# Controller_Board.net
KiCad netlist of a schematic drawn in EAGLE
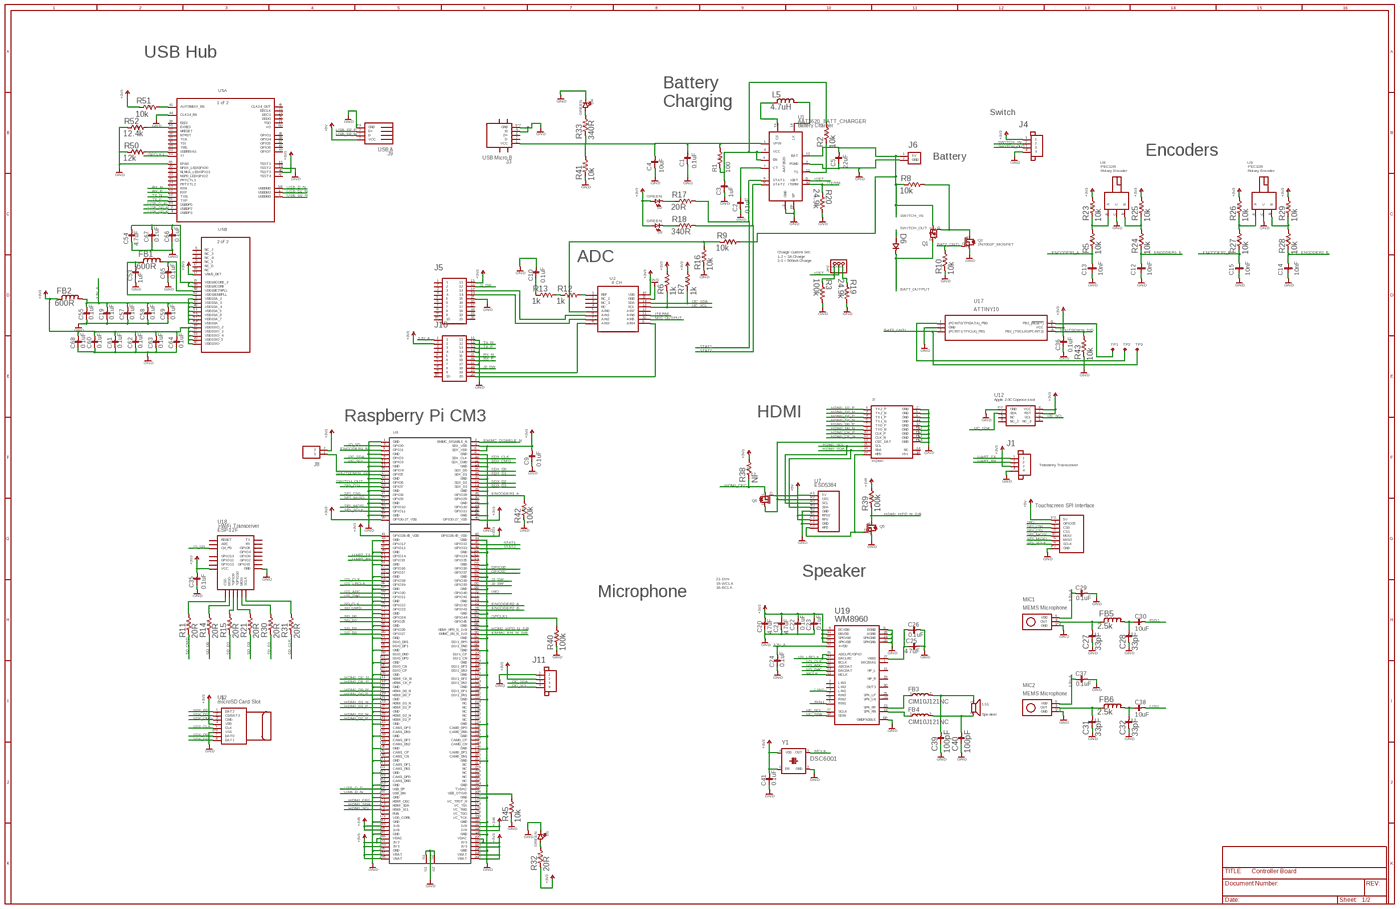
[diagram p0: schematic, sheet 1, overview]
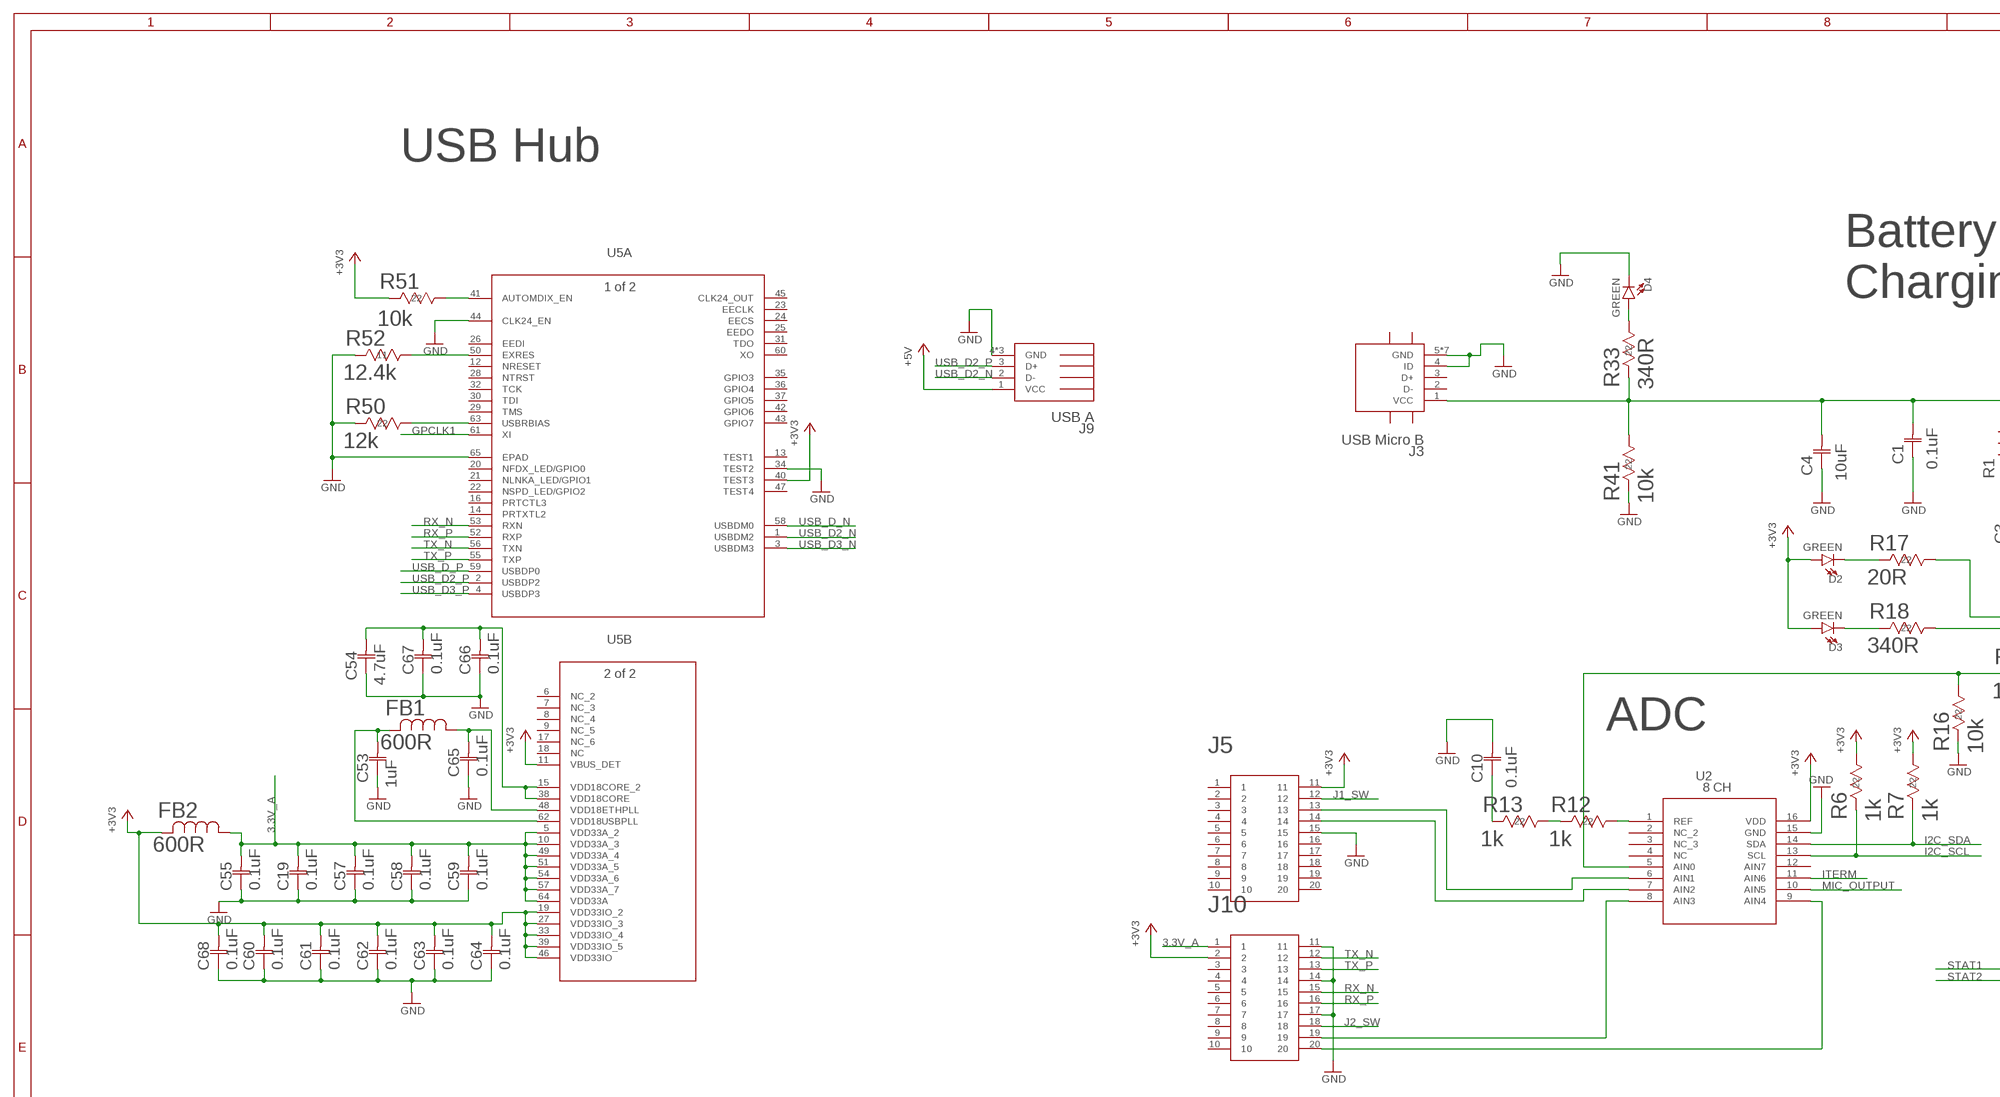
[diagram p1: schematic, sheet 1, part 1 of 4]
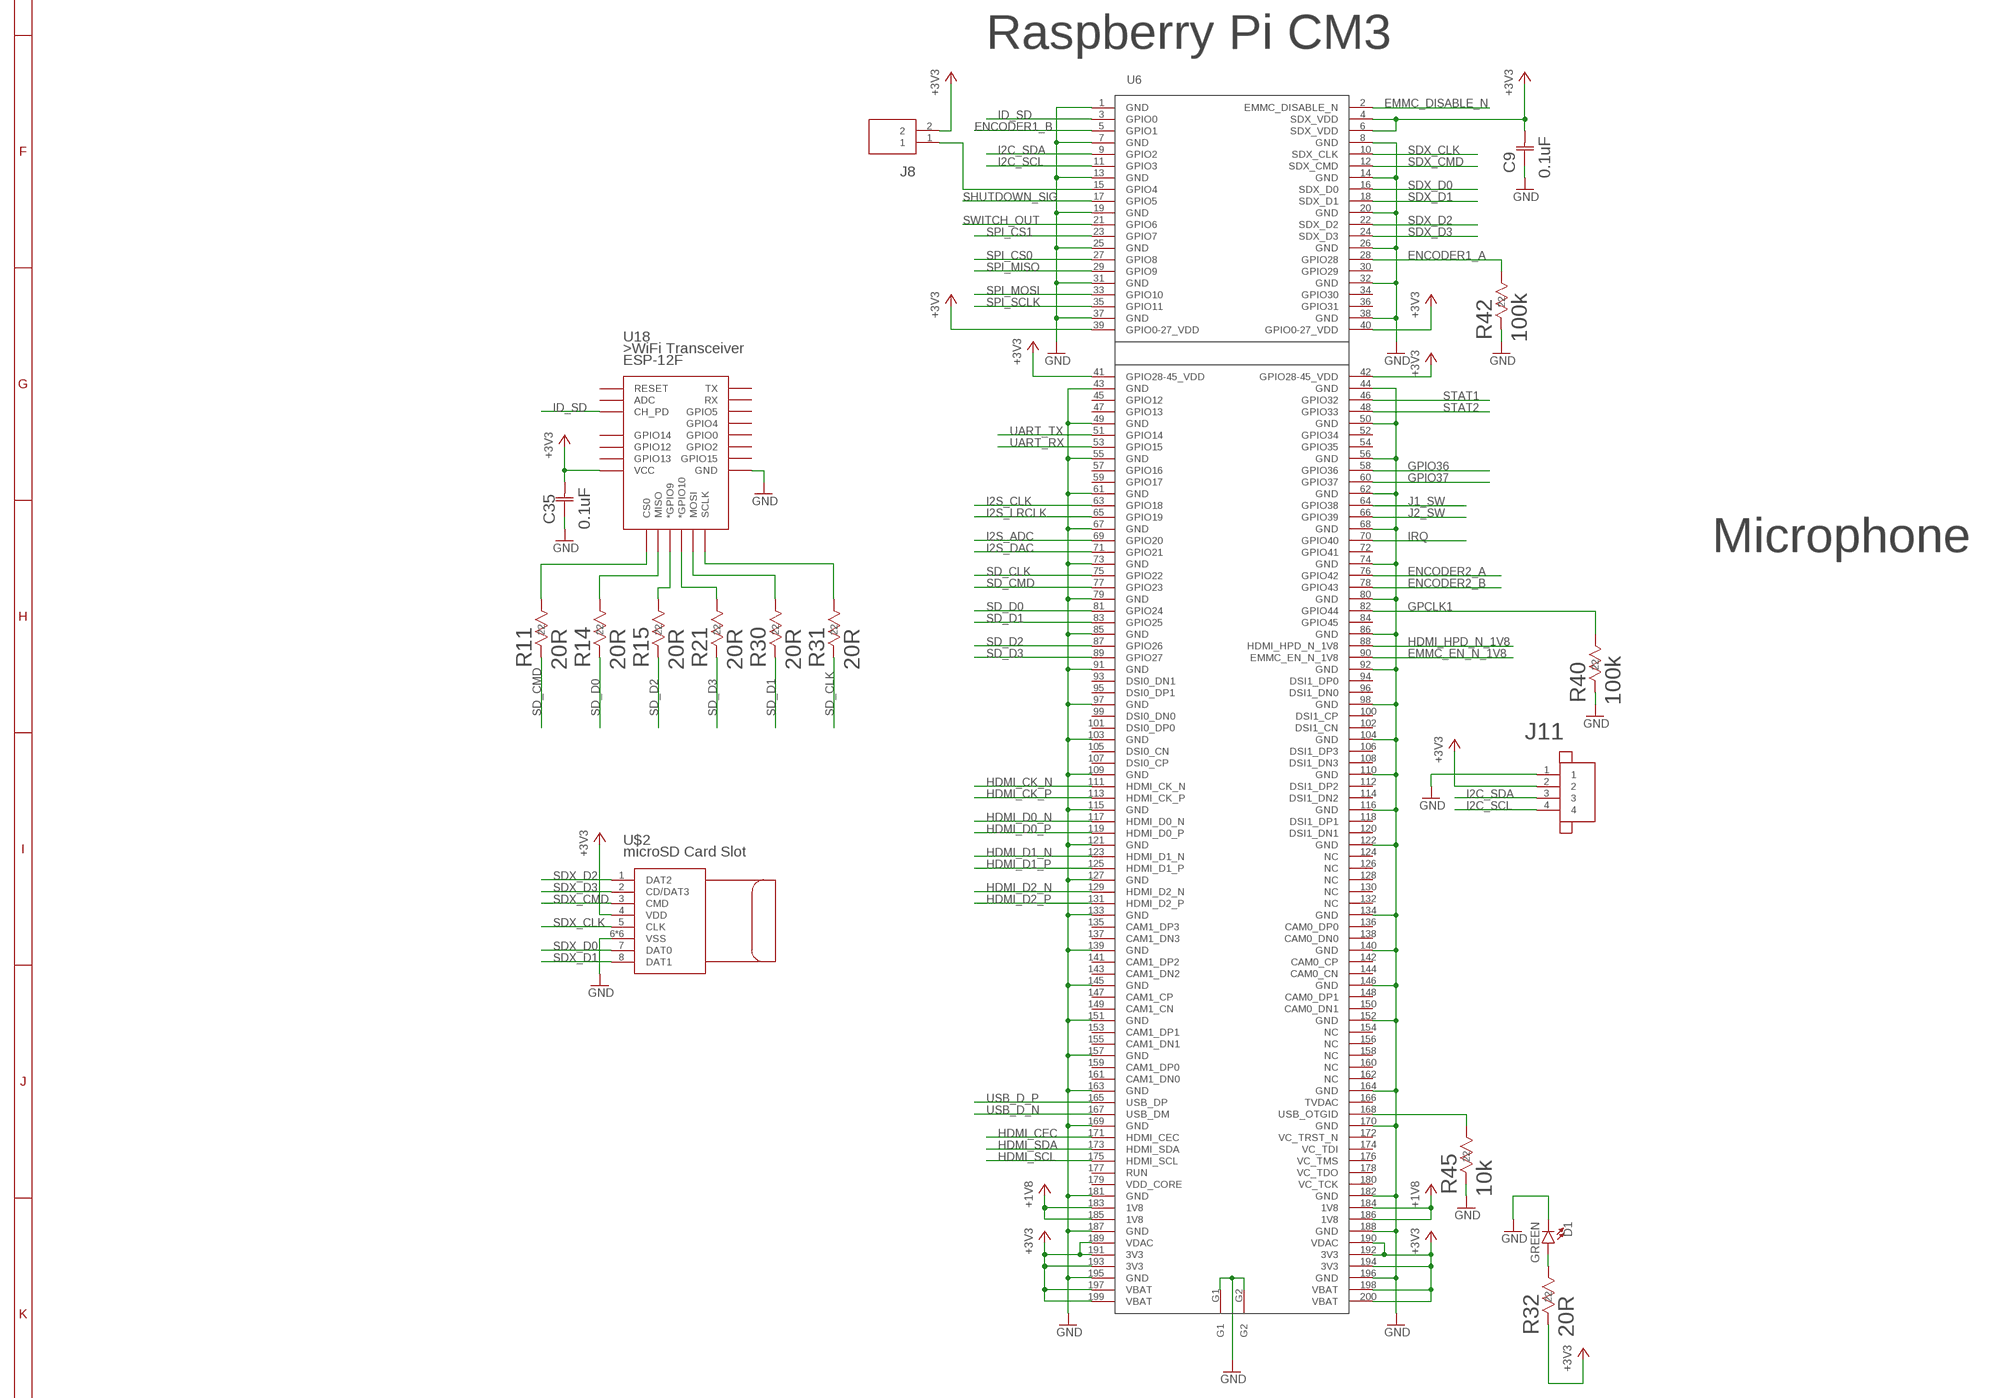
[diagram p2: schematic, sheet 1, part 2 of 4]
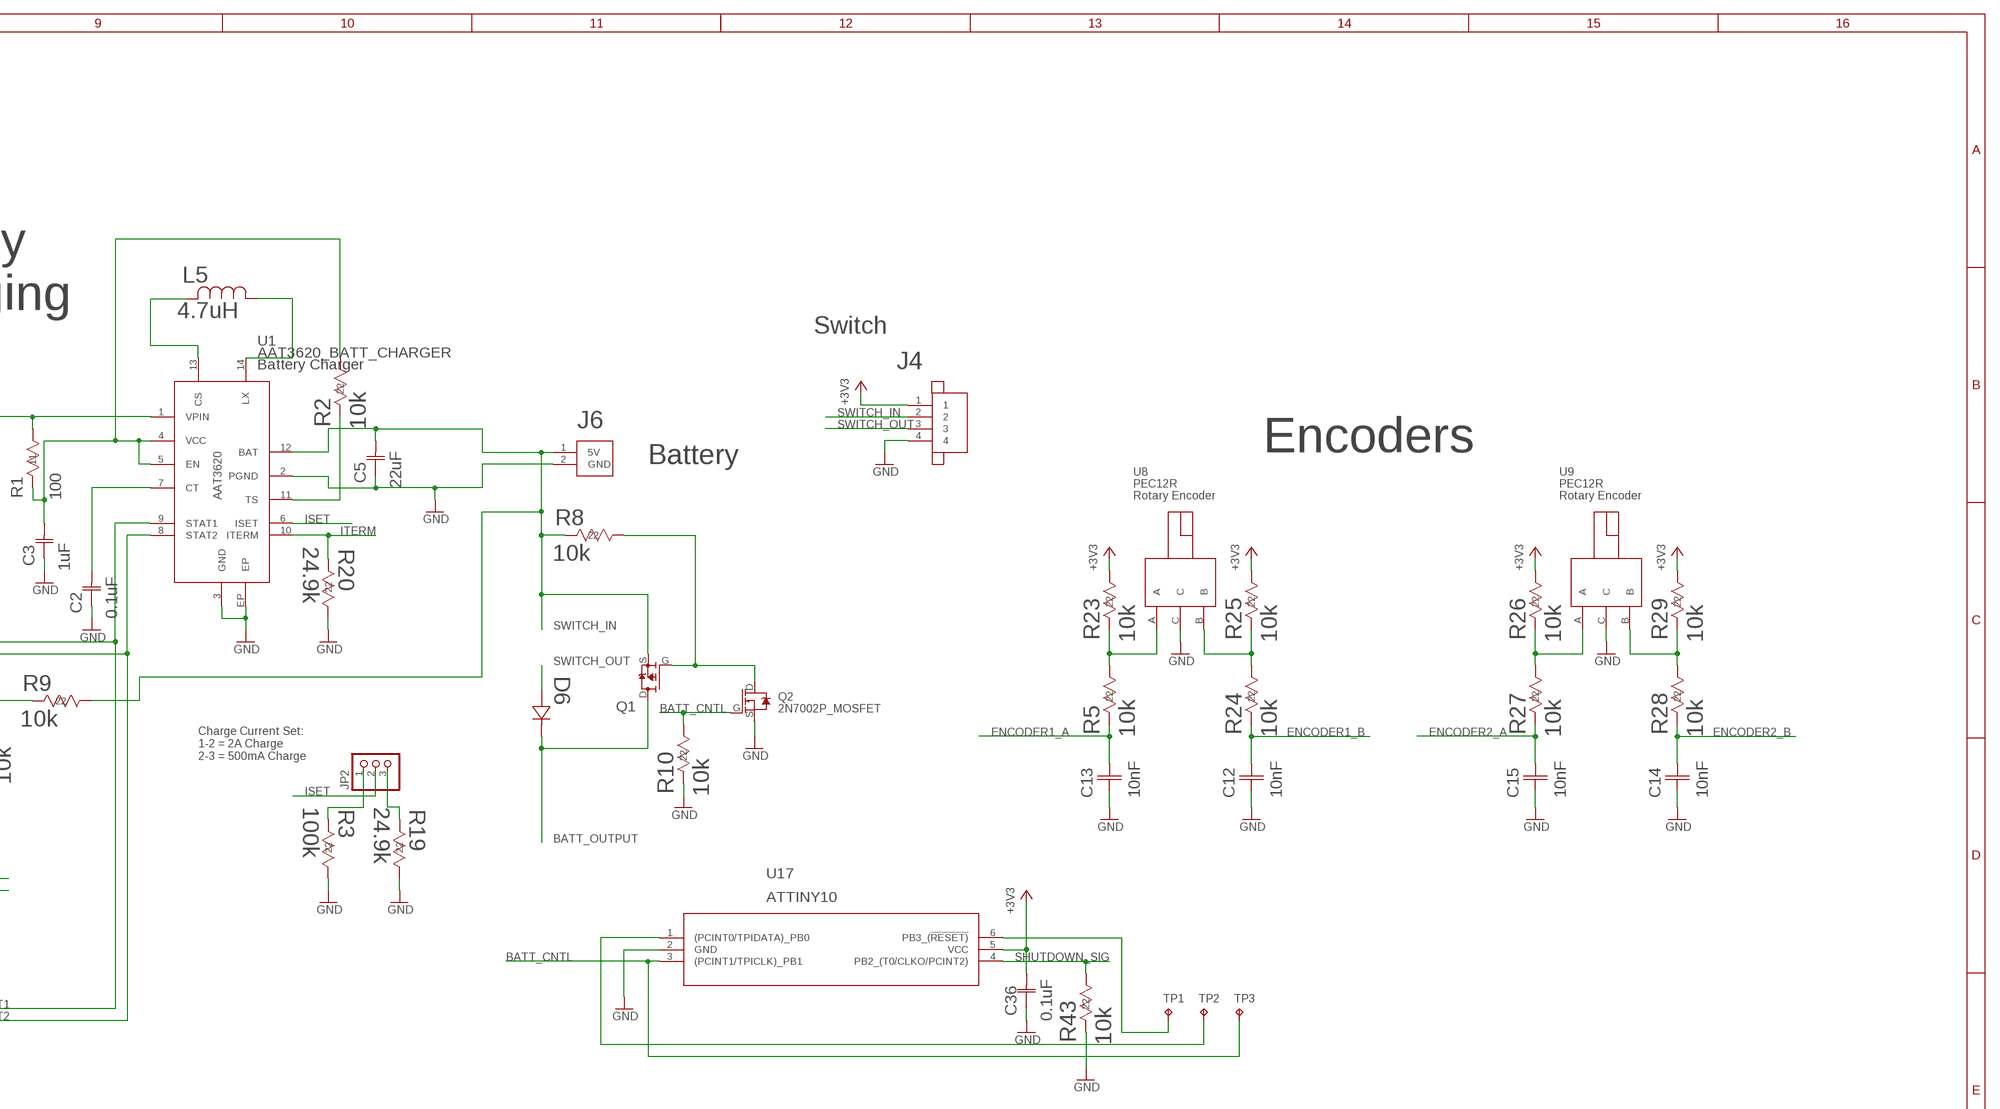
[diagram p3: schematic, sheet 1, part 3 of 4]
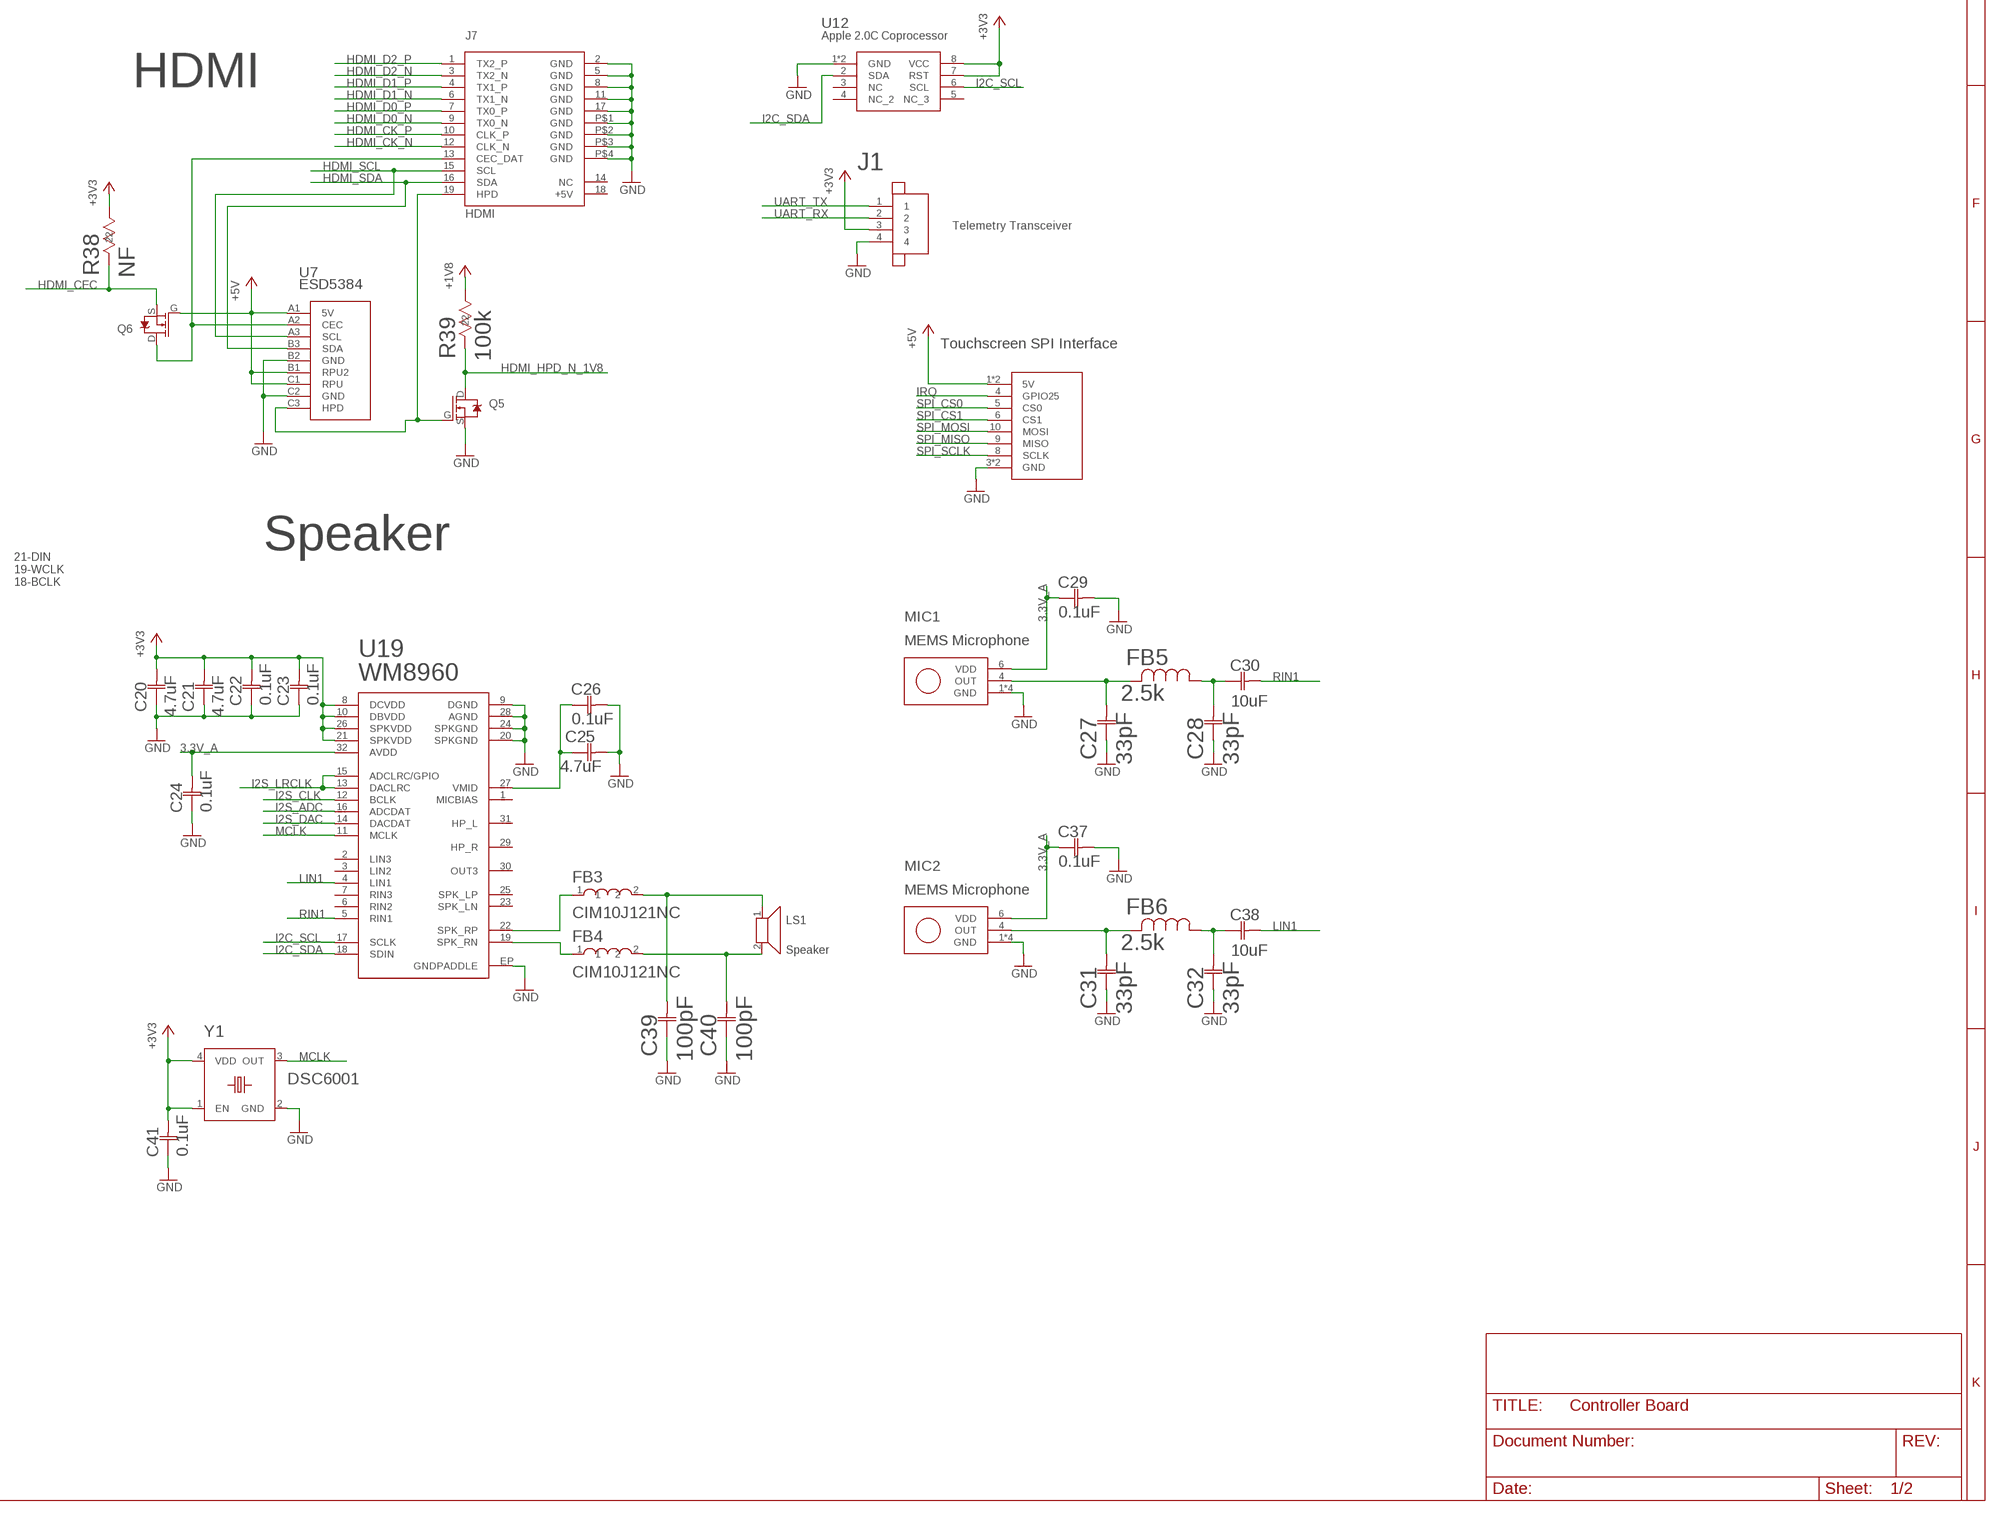
[diagram p4: schematic, sheet 1, part 4 of 4]
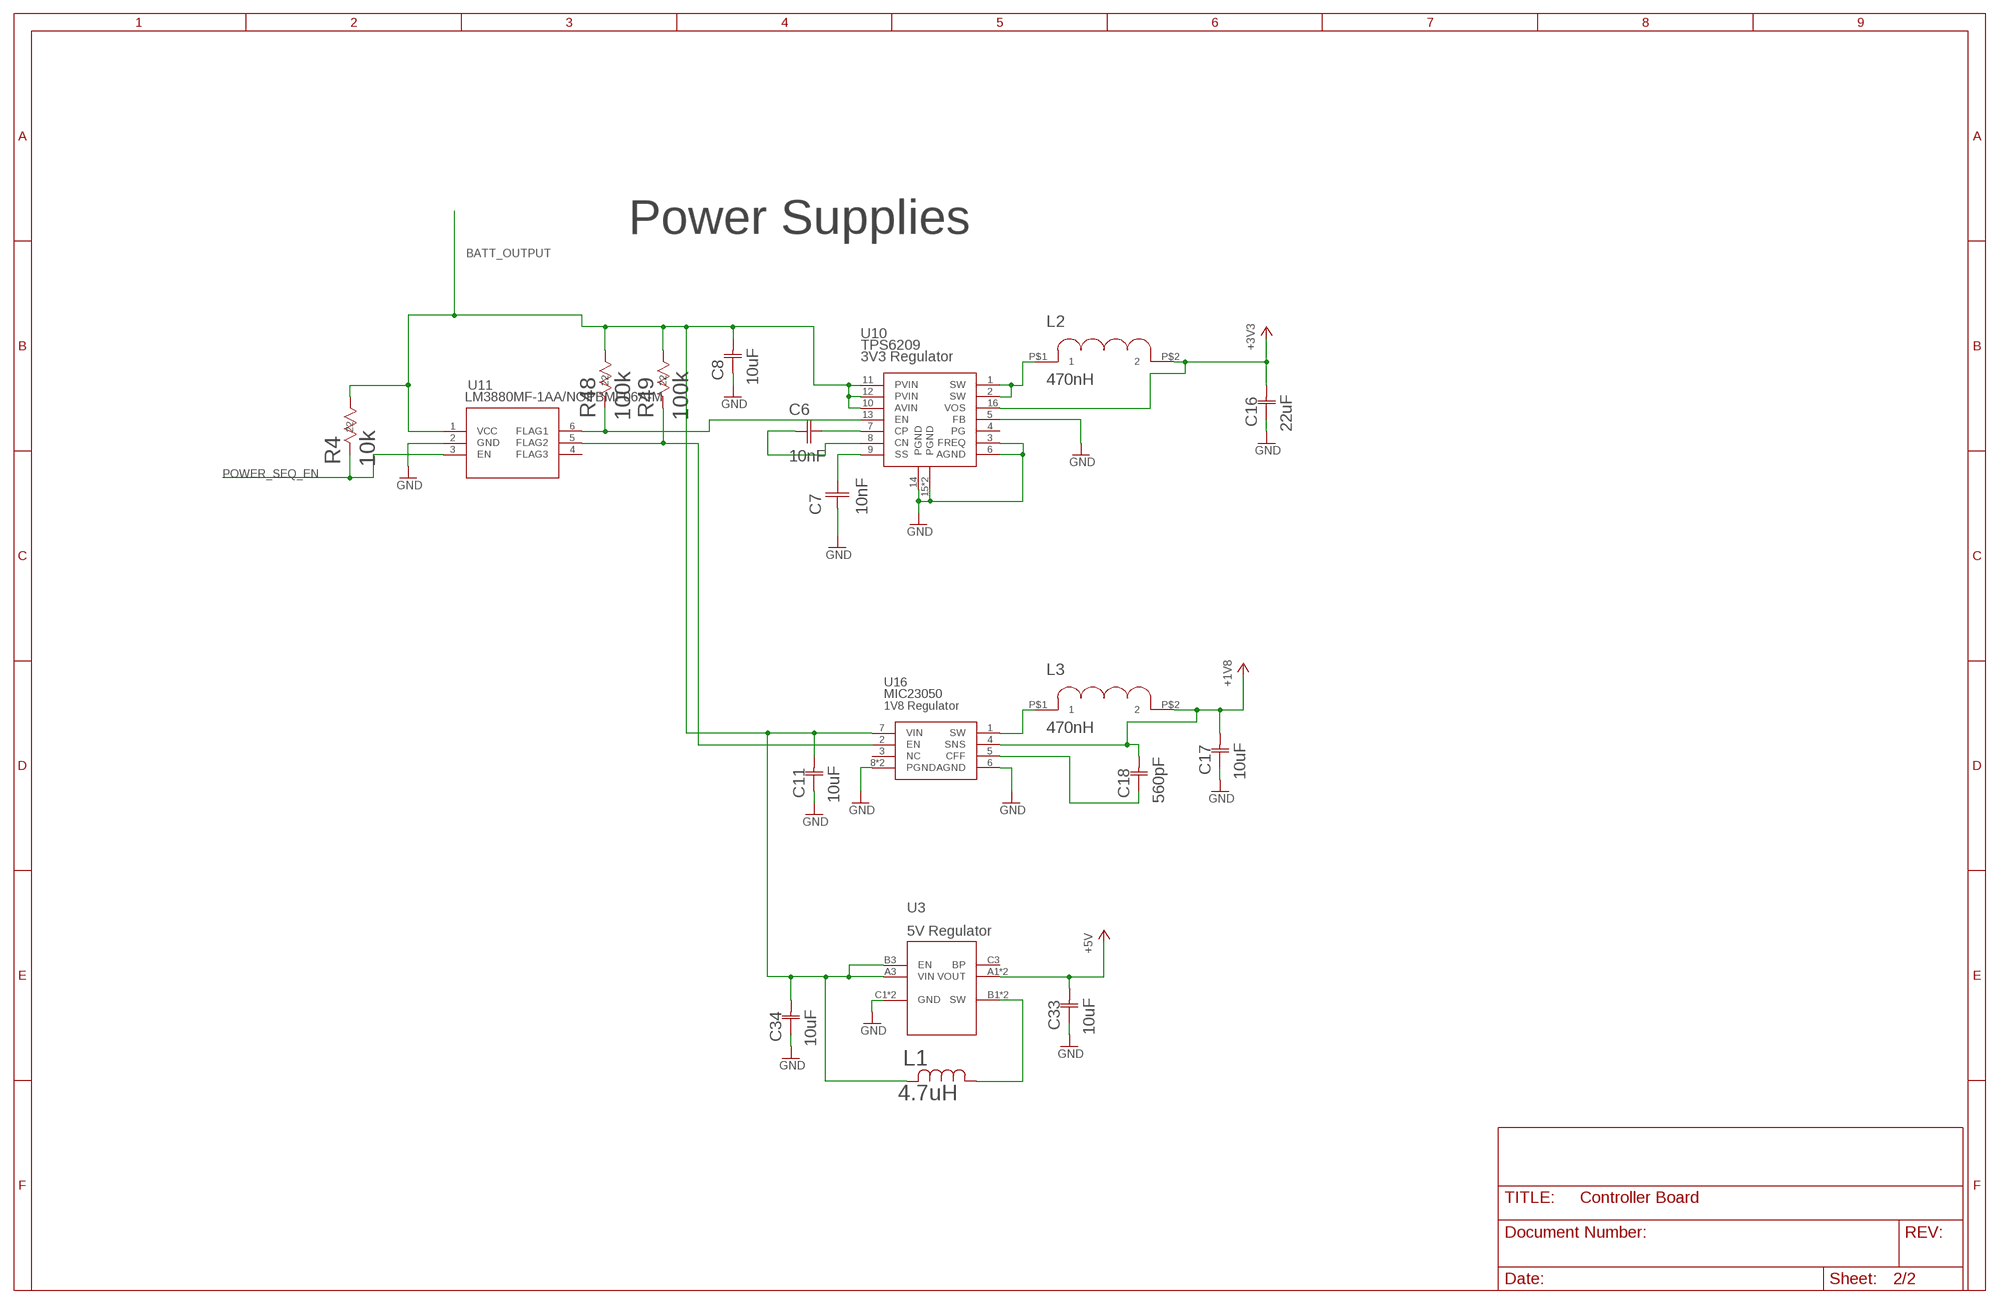
[diagram p5: schematic, sheet 2]

(export (version "E")
  (design (tool "Eeschema 10.0.6"))
  (components
    (comp (ref "C1")
      (value "0.1uF")
      (footprint "eagle-import:0805")
      (fields
        (field (name "MANUFACTURER_PART_NUMBER") "08055C104KAT2A")
        (field (name "COPYRIGHT") "Copyright C 2015 Accelerated Designs. All rights reserved")
      )
      (libsource (lib "eagle-import") (part "08055C104KAT2A"))
    )
    (comp (ref "C2")
      (value "0.1uF")
      (footprint "eagle-import:0805")
      (fields
        (field (name "MANUFACTURER_PART_NUMBER") "08055C104KAT2A")
        (field (name "COPYRIGHT") "Copyright C 2015 Accelerated Designs. All rights reserved")
      )
      (libsource (lib "eagle-import") (part "08055C104KAT2A"))
    )
    (comp (ref "C3")
      (value "1uF")
      (footprint "eagle-import:YAG_CC0805")
      (fields
        (field (name "MANUFACTURER_PART_NUMBER") "CC0805KKX7R7BB105")
        (field (name "COPYRIGHT") "Copyright C 2015 Accelerated Designs. All rights reserved")
      )
      (libsource (lib "eagle-import") (part "Controller Board_178037_CC0805KKX7R7BB105"))
    )
    (comp (ref "C4")
      (value "10uF")
      (footprint "eagle-import:G-21")
      (fields
        (field (name "MANUFACTURER_PART_NUMBER") "GRM21BR60J106ME19L")
        (field (name "COPYRIGHT") "Copyright C 2015 Accelerated Designs. All rights reserved")
      )
      (libsource (lib "eagle-import") (part "Controller Board_178037_GRM21BR60J106ME19L"))
    )
    (comp (ref "C5")
      (value "22uF")
      (footprint "eagle-import:G-21")
      (fields
        (field (name "MANUFACTURER_PART_NUMBER") "GRM21BR60J226ME39L")
        (field (name "COPYRIGHT") "Copyright C 2015 Accelerated Designs. All rights reserved")
      )
      (libsource (lib "eagle-import") (part "GRM21BR60J226ME39L"))
    )
    (comp (ref "C9")
      (value "0.1uF")
      (footprint "eagle-import:0805")
      (fields
        (field (name "MANUFACTURER_PART_NUMBER") "08055C104KAT2A")
        (field (name "COPYRIGHT") "Copyright C 2015 Accelerated Designs. All rights reserved")
      )
      (libsource (lib "eagle-import") (part "08055C104KAT2A"))
    )
    (comp (ref "C10")
      (value "0.1uF")
      (footprint "eagle-import:0805")
      (fields
        (field (name "MANUFACTURER_PART_NUMBER") "08055C104KAT2A")
        (field (name "COPYRIGHT") "Copyright C 2015 Accelerated Designs. All rights reserved")
      )
      (libsource (lib "eagle-import") (part "08055C104KAT2A"))
    )
    (comp (ref "C12")
      (value "10nF")
      (footprint "eagle-import:0603_CAPACITOR")
      (libsource (lib "eagle-import") (part "10NF_CAPACITOR"))
    )
    (comp (ref "C13")
      (value "10nF")
      (footprint "eagle-import:0603_CAPACITOR")
      (libsource (lib "eagle-import") (part "10NF_CAPACITOR"))
    )
    (comp (ref "C14")
      (value "10nF")
      (footprint "eagle-import:0603_CAPACITOR")
      (libsource (lib "eagle-import") (part "10NF_CAPACITOR"))
    )
    (comp (ref "C15")
      (value "10nF")
      (footprint "eagle-import:0603_CAPACITOR")
      (libsource (lib "eagle-import") (part "10NF_CAPACITOR"))
    )
    (comp (ref "C19")
      (value "0.1uF")
      (footprint "eagle-import:0402-M")
      (fields (field (name "MANUFACTURER_PART_NUMBER") "0402ZD104KAT2A"))
      (libsource (lib "eagle-import") (part "0402ZD104KAT2A0402-M"))
    )
    (comp (ref "C20")
      (value "4.7uF")
      (footprint "eagle-import:0603-M")
      (fields (field (name "MANUFACTURER_PART_NUMBER") "06036D475KAT2A"))
      (libsource (lib "eagle-import") (part "06036D475KAT2A0603-M"))
    )
    (comp (ref "C21")
      (value "4.7uF")
      (footprint "eagle-import:0603-M")
      (fields (field (name "MANUFACTURER_PART_NUMBER") "06036D475KAT2A"))
      (libsource (lib "eagle-import") (part "06036D475KAT2A0603-M"))
    )
    (comp (ref "C22")
      (value "0.1uF")
      (footprint "eagle-import:0402-M")
      (fields (field (name "MANUFACTURER_PART_NUMBER") "0402ZD104KAT2A"))
      (libsource (lib "eagle-import") (part "0402ZD104KAT2A0402-M"))
    )
    (comp (ref "C23")
      (value "0.1uF")
      (footprint "eagle-import:0402-M")
      (fields (field (name "MANUFACTURER_PART_NUMBER") "0402ZD104KAT2A"))
      (libsource (lib "eagle-import") (part "0402ZD104KAT2A0402-M"))
    )
    (comp (ref "C24")
      (value "0.1uF")
      (footprint "eagle-import:0402-M")
      (fields (field (name "MANUFACTURER_PART_NUMBER") "0402ZD104KAT2A"))
      (libsource (lib "eagle-import") (part "0402ZD104KAT2A0402-M"))
    )
    (comp (ref "C25")
      (value "4.7uF")
      (footprint "eagle-import:0603-M")
      (fields (field (name "MANUFACTURER_PART_NUMBER") "06036D475KAT2A"))
      (libsource (lib "eagle-import") (part "06036D475KAT2A0603-M"))
    )
    (comp (ref "C26")
      (value "0.1uF")
      (footprint "eagle-import:0402-M")
      (fields (field (name "MANUFACTURER_PART_NUMBER") "0402ZD104KAT2A"))
      (libsource (lib "eagle-import") (part "0402ZD104KAT2A0402-M"))
    )
    (comp (ref "C27")
      (value "33pF")
      (footprint "eagle-import:G-155-M")
      (fields (field (name "MANUFACTURER_PART_NUMBER") "GRM1555C1H330JA01D"))
      (libsource (lib "eagle-import") (part "GRM1555C1H330JA01DG-155-M"))
    )
    (comp (ref "C28")
      (value "33pF")
      (footprint "eagle-import:G-155-M")
      (fields (field (name "MANUFACTURER_PART_NUMBER") "GRM1555C1H330JA01D"))
      (libsource (lib "eagle-import") (part "GRM1555C1H330JA01DG-155-M"))
    )
    (comp (ref "C29")
      (value "0.1uF")
      (footprint "eagle-import:0402-M")
      (fields (field (name "MANUFACTURER_PART_NUMBER") "0402ZD104KAT2A"))
      (libsource (lib "eagle-import") (part "0402ZD104KAT2A0402-M"))
    )
    (comp (ref "C30")
      (value "10uF")
      (footprint "eagle-import:G-21")
      (fields
        (field (name "MANUFACTURER_PART_NUMBER") "GRM21BR60J106ME19L")
        (field (name "COPYRIGHT") "Copyright C 2015 Accelerated Designs. All rights reserved")
      )
      (libsource (lib "eagle-import") (part "GRM21BR60J106ME19L"))
    )
    (comp (ref "C31")
      (value "33pF")
      (footprint "eagle-import:G-155-M")
      (fields (field (name "MANUFACTURER_PART_NUMBER") "GRM1555C1H330JA01D"))
      (libsource (lib "eagle-import") (part "GRM1555C1H330JA01DG-155-M"))
    )
    (comp (ref "C32")
      (value "33pF")
      (footprint "eagle-import:G-155-M")
      (fields (field (name "MANUFACTURER_PART_NUMBER") "GRM1555C1H330JA01D"))
      (libsource (lib "eagle-import") (part "GRM1555C1H330JA01DG-155-M"))
    )
    (comp (ref "C35")
      (value "0.1uF")
      (footprint "eagle-import:0805")
      (fields
        (field (name "MANUFACTURER_PART_NUMBER") "08055C104KAT2A")
        (field (name "COPYRIGHT") "Copyright C 2015 Accelerated Designs. All rights reserved")
      )
      (libsource (lib "eagle-import") (part "08055C104KAT2A"))
    )
    (comp (ref "C36")
      (value "0.1uF")
      (footprint "eagle-import:0805")
      (fields
        (field (name "MANUFACTURER_PART_NUMBER") "08055C104KAT2A")
        (field (name "COPYRIGHT") "Copyright C 2015 Accelerated Designs. All rights reserved")
      )
      (libsource (lib "eagle-import") (part "08055C104KAT2A"))
    )
    (comp (ref "C37")
      (value "0.1uF")
      (footprint "eagle-import:0402-M")
      (fields (field (name "MANUFACTURER_PART_NUMBER") "0402ZD104KAT2A"))
      (libsource (lib "eagle-import") (part "0402ZD104KAT2A0402-M"))
    )
    (comp (ref "C38")
      (value "10uF")
      (footprint "eagle-import:G-21")
      (fields
        (field (name "MANUFACTURER_PART_NUMBER") "GRM21BR60J106ME19L")
        (field (name "COPYRIGHT") "Copyright C 2015 Accelerated Designs. All rights reserved")
      )
      (libsource (lib "eagle-import") (part "GRM21BR60J106ME19L"))
    )
    (comp (ref "C39")
      (value "100pF")
      (footprint "eagle-import:YAG_CC0402-M")
      (fields (field (name "MANUFACTURER_PART_NUMBER") "CC0402KRX7R9BB101"))
      (libsource (lib "eagle-import") (part "CC0402KRX7R9BB101YAG_CC0402-M"))
    )
    (comp (ref "C40")
      (value "100pF")
      (footprint "eagle-import:YAG_CC0402-M")
      (fields (field (name "MANUFACTURER_PART_NUMBER") "CC0402KRX7R9BB101"))
      (libsource (lib "eagle-import") (part "CC0402KRX7R9BB101YAG_CC0402-M"))
    )
    (comp (ref "C41")
      (value "0.1uF")
      (footprint "eagle-import:0402-M")
      (fields (field (name "MANUFACTURER_PART_NUMBER") "0402ZD104KAT2A"))
      (libsource (lib "eagle-import") (part "0402ZD104KAT2A0402-M"))
    )
    (comp (ref "C53")
      (value "1uF")
      (footprint "eagle-import:YAG_CC0805")
      (fields
        (field (name "MANUFACTURER_PART_NUMBER") "CC0805KKX7R7BB105")
        (field (name "COPYRIGHT") "Copyright C 2015 Accelerated Designs. All rights reserved")
      )
      (libsource (lib "eagle-import") (part "CC0805KKX7R7BB105"))
    )
    (comp (ref "C54")
      (value "4.7uF")
      (footprint "eagle-import:0603-M")
      (fields (field (name "MANUFACTURER_PART_NUMBER") "06036D475KAT2A"))
      (libsource (lib "eagle-import") (part "06036D475KAT2A0603-M"))
    )
    (comp (ref "C55")
      (value "0.1uF")
      (footprint "eagle-import:0402-M")
      (fields (field (name "MANUFACTURER_PART_NUMBER") "0402ZD104KAT2A"))
      (libsource (lib "eagle-import") (part "0402ZD104KAT2A0402-M"))
    )
    (comp (ref "C57")
      (value "0.1uF")
      (footprint "eagle-import:0402-M")
      (fields (field (name "MANUFACTURER_PART_NUMBER") "0402ZD104KAT2A"))
      (libsource (lib "eagle-import") (part "0402ZD104KAT2A0402-M"))
    )
    (comp (ref "C58")
      (value "0.1uF")
      (footprint "eagle-import:0402-M")
      (fields (field (name "MANUFACTURER_PART_NUMBER") "0402ZD104KAT2A"))
      (libsource (lib "eagle-import") (part "0402ZD104KAT2A0402-M"))
    )
    (comp (ref "C59")
      (value "0.1uF")
      (footprint "eagle-import:0402-M")
      (fields (field (name "MANUFACTURER_PART_NUMBER") "0402ZD104KAT2A"))
      (libsource (lib "eagle-import") (part "0402ZD104KAT2A0402-M"))
    )
    (comp (ref "C60")
      (value "0.1uF")
      (footprint "eagle-import:0402-M")
      (fields (field (name "MANUFACTURER_PART_NUMBER") "0402ZD104KAT2A"))
      (libsource (lib "eagle-import") (part "0402ZD104KAT2A0402-M"))
    )
    (comp (ref "C61")
      (value "0.1uF")
      (footprint "eagle-import:0402-M")
      (fields (field (name "MANUFACTURER_PART_NUMBER") "0402ZD104KAT2A"))
      (libsource (lib "eagle-import") (part "0402ZD104KAT2A0402-M"))
    )
    (comp (ref "C62")
      (value "0.1uF")
      (footprint "eagle-import:0402-M")
      (fields (field (name "MANUFACTURER_PART_NUMBER") "0402ZD104KAT2A"))
      (libsource (lib "eagle-import") (part "0402ZD104KAT2A0402-M"))
    )
    (comp (ref "C63")
      (value "0.1uF")
      (footprint "eagle-import:0402-M")
      (fields (field (name "MANUFACTURER_PART_NUMBER") "0402ZD104KAT2A"))
      (libsource (lib "eagle-import") (part "0402ZD104KAT2A0402-M"))
    )
    (comp (ref "C64")
      (value "0.1uF")
      (footprint "eagle-import:0402-M")
      (fields (field (name "MANUFACTURER_PART_NUMBER") "0402ZD104KAT2A"))
      (libsource (lib "eagle-import") (part "0402ZD104KAT2A0402-M"))
    )
    (comp (ref "C65")
      (value "0.1uF")
      (footprint "eagle-import:0402-M")
      (fields (field (name "MANUFACTURER_PART_NUMBER") "0402ZD104KAT2A"))
      (libsource (lib "eagle-import") (part "0402ZD104KAT2A0402-M"))
    )
    (comp (ref "C66")
      (value "0.1uF")
      (footprint "eagle-import:0402-M")
      (fields (field (name "MANUFACTURER_PART_NUMBER") "0402ZD104KAT2A"))
      (libsource (lib "eagle-import") (part "0402ZD104KAT2A0402-M"))
    )
    (comp (ref "C67")
      (value "0.1uF")
      (footprint "eagle-import:0402-M")
      (fields (field (name "MANUFACTURER_PART_NUMBER") "0402ZD104KAT2A"))
      (libsource (lib "eagle-import") (part "0402ZD104KAT2A0402-M"))
    )
    (comp (ref "C68")
      (value "0.1uF")
      (footprint "eagle-import:0402-M")
      (fields (field (name "MANUFACTURER_PART_NUMBER") "0402ZD104KAT2A"))
      (libsource (lib "eagle-import") (part "0402ZD104KAT2A0402-M"))
    )
    (comp (ref "D1")
      (value "GREEN")
      (footprint "eagle-import:LED-0603")
      (libsource (lib "eagle-import") (part "LED-GREEN0603"))
    )
    (comp (ref "D2")
      (value "GREEN")
      (footprint "eagle-import:LED-0603")
      (libsource (lib "eagle-import") (part "LED-GREEN0603"))
    )
    (comp (ref "D3")
      (value "GREEN")
      (footprint "eagle-import:LED-0603")
      (libsource (lib "eagle-import") (part "LED-GREEN0603"))
    )
    (comp (ref "D4")
      (value "GREEN")
      (footprint "eagle-import:LED-0603")
      (libsource (lib "eagle-import") (part "LED-GREEN0603"))
    )
    (comp (ref "D6")
      (value "1N4148W-7-FSOD123-M")
      (footprint "eagle-import:SOD123-M")
      (fields
        (field (name "MANUFACTURER_PART_NUMBER") "1N4148W7F")
        (field (name "COPYRIGHT") "Copyright C 2015 Accelerated Designs. All rights reserved")
      )
      (libsource (lib "eagle-import") (part "1N4148W-7-FSOD123-M"))
    )
    (comp (ref "FB1")
      (value "600R")
      (footprint "eagle-import:IND_BLM18_0603-M")
      (fields (field (name "MANUFACTURER_PART_NUMBER") "BLM18AG601SN1D"))
      (libsource (lib "eagle-import") (part "BLM18AG601SN1DIND_BLM18_0603-M"))
    )
    (comp (ref "FB2")
      (value "600R")
      (footprint "eagle-import:IND_BLM18_0603-M")
      (fields (field (name "MANUFACTURER_PART_NUMBER") "BLM18AG601SN1D"))
      (libsource (lib "eagle-import") (part "BLM18AG601SN1DIND_BLM18_0603-M"))
    )
    (comp (ref "FB3")
      (value "CIM10J121NC")
      (footprint "eagle-import:0603_CAPACITOR")
      (libsource (lib "eagle-import") (part "CIM10J121NC"))
    )
    (comp (ref "FB4")
      (value "CIM10J121NC")
      (footprint "eagle-import:0603_CAPACITOR")
      (libsource (lib "eagle-import") (part "CIM10J121NC"))
    )
    (comp (ref "FB5")
      (value "2.5k")
      (footprint "eagle-import:IND_BLM18_0603-M")
      (fields (field (name "MANUFACTURER_PART_NUMBER") "BLM18BD252SN1D"))
      (libsource (lib "eagle-import") (part "BLM18BD252SN1DIND_BLM18_0603-M"))
    )
    (comp (ref "FB6")
      (value "2.5k")
      (footprint "eagle-import:IND_BLM18_0603-M")
      (fields (field (name "MANUFACTURER_PART_NUMBER") "BLM18BD252SN1D"))
      (libsource (lib "eagle-import") (part "BLM18BD252SN1DIND_BLM18_0603-M"))
    )
    (comp (ref "J1")
      (value "JST_SH_4POS")
      (footprint "eagle-import:JST_SH_4POS")
      (libsource (lib "eagle-import") (part "JST_SH_4POS"))
    )
    (comp (ref "J2")
      (value "3.5_TOUCHSCREEN")
      (footprint "eagle-import:3.5_TOUCHSCREEN")
      (libsource (lib "eagle-import") (part "3.5_TOUCHSCREEN"))
    )
    (comp (ref "J3")
      (value "USB_MICRO_B_SMT")
      (footprint "eagle-import:USB_MICRO_B_SMT")
      (libsource (lib "eagle-import") (part "USB_MICRO_B_SMT"))
    )
    (comp (ref "J4")
      (value "JST_SH_4POS")
      (footprint "eagle-import:JST_SH_4POS")
      (libsource (lib "eagle-import") (part "JST_SH_4POS"))
    )
    (comp (ref "J5")
      (value "EDGE_CONNECTOR_20POS")
      (footprint "eagle-import:EDGE_CONNECTOR_20POS")
      (libsource (lib "eagle-import") (part "EDGE_CONNECTOR_20POS"))
    )
    (comp (ref "J6")
      (value "POWER_CONNECTOR")
      (footprint "eagle-import:XH_CONNECTOR")
      (libsource (lib "eagle-import") (part "POWER_CONNECTOR"))
    )
    (comp (ref "J7")
      (value "HDMI")
      (footprint "eagle-import:HDMI")
      (libsource (lib "eagle-import") (part "HDMI"))
    )
    (comp (ref "J8")
      (value "2_PIN_CONNECTOR")
      (footprint "eagle-import:XH_CONNECTOR")
      (libsource (lib "eagle-import") (part "2_PIN_CONNECTOR"))
    )
    (comp (ref "J9")
      (value "USB_A_RECEPT")
      (footprint "eagle-import:USB_A_RECEPT")
      (libsource (lib "eagle-import") (part "USB_A_RECEPT"))
    )
    (comp (ref "J10")
      (value "EDGE_CONNECTOR_20POS")
      (footprint "eagle-import:EDGE_CONNECTOR_20POS")
      (libsource (lib "eagle-import") (part "EDGE_CONNECTOR_20POS"))
    )
    (comp (ref "J11")
      (value "JST_SH_4POS")
      (footprint "eagle-import:JST_SH_4POS")
      (libsource (lib "eagle-import") (part "JST_SH_4POS"))
    )
    (comp (ref "JP2")
      (value "PINHD-1X3")
      (footprint "eagle-import:1X03")
      (libsource (lib "eagle-import") (part "PINHD-1X3"))
    )
    (comp (ref "L5")
      (value "4.7uH")
      (footprint "eagle-import:1008")
      (libsource (lib "eagle-import") (part "DFE252012P-4R7M=P2{dblquote}"))
    )
    (comp (ref "LS1")
      (value "SP-1510")
      (footprint "eagle-import:SPEAKER")
      (libsource (lib "eagle-import") (part "SP-1510"))
    )
    (comp (ref "MIC1")
      (value "SPH1642HT5H-1")
      (footprint "eagle-import:SISONIC_MICROPHONE")
      (libsource (lib "eagle-import") (part "SPH1642HT5H-1"))
    )
    (comp (ref "MIC2")
      (value "SPH1642HT5H-1")
      (footprint "eagle-import:SISONIC_MICROPHONE")
      (libsource (lib "eagle-import") (part "SPH1642HT5H-1"))
    )
    (comp (ref "Q1")
      (value "DMP3099L")
      (footprint "eagle-import:SOT-23_(TO-236AB)")
      (libsource (lib "eagle-import") (part "DMP3099L"))
    )
    (comp (ref "Q2")
      (value "2N7002P_MOSFET")
      (footprint "eagle-import:SOT-23_(TO-236AB)")
      (libsource (lib "eagle-import") (part "2N7002P_MOSFET"))
    )
    (comp (ref "Q5")
      (value "DMG1012T")
      (footprint "eagle-import:SOT-523")
      (libsource (lib "eagle-import") (part "DMG1012T"))
    )
    (comp (ref "Q6")
      (value "DMG1012T")
      (footprint "eagle-import:SOT-523")
      (libsource (lib "eagle-import") (part "DMG1012T"))
    )
    (comp (ref "R1")
      (value "100")
      (footprint "eagle-import:1206")
      (libsource (lib "eagle-import") (part "100_RESISTOR"))
    )
    (comp (ref "R2")
      (value "10k")
      (footprint "eagle-import:RC0805N")
      (fields
        (field (name "DIGIKEYPARTNUMBER") "P10KDATRND")
        (field (name "MANUFACTURER_PART_NUMBER") "ERA6AEB103V")
        (field (name "TOLERANCE") "0.1%")
        (field (name "COPYRIGHT") "Copyright C 2015 Accelerated Designs. All rights reserved")
      )
      (libsource (lib "eagle-import") (part "Controller Board_178037_ERA-6AEB103V"))
    )
    (comp (ref "R3")
      (value "100k")
      (footprint "eagle-import:RC0603N-M")
      (fields (field (name "MANUFACTURER_PART_NUMBER") "RC0603JR07100KL"))
      (libsource (lib "eagle-import") (part "RC0603JR-07100KLRC0603N-M"))
    )
    (comp (ref "R5")
      (value "10k")
      (footprint "eagle-import:RC0805N")
      (fields
        (field (name "DIGIKEYPARTNUMBER") "P10KDATRND")
        (field (name "MANUFACTURER_PART_NUMBER") "ERA6AEB103V")
        (field (name "TOLERANCE") "0.1%")
        (field (name "COPYRIGHT") "Copyright C 2015 Accelerated Designs. All rights reserved")
      )
      (libsource (lib "eagle-import") (part "Controller Board_178037_ERA-6AEB103V"))
    )
    (comp (ref "R6")
      (value "1k")
      (footprint "eagle-import:RC0603N-M")
      (fields
        (field (name "DIGIKEYPARTNUMBER") "3111.0KGRTRND")
        (field (name "MANUFACTURER_PART_NUMBER") "RC0603JR071KL")
        (field (name "NEWARKPARTNUMBER") "14M7231")
        (field (name "COPYRIGHT") "Copyright C 2015 Accelerated Designs. All rights reserved")
      )
      (libsource (lib "eagle-import") (part "RC0603JR-071KLRC0603N-M"))
    )
    (comp (ref "R7")
      (value "1k")
      (footprint "eagle-import:RC0603N-M")
      (fields
        (field (name "DIGIKEYPARTNUMBER") "3111.0KGRTRND")
        (field (name "MANUFACTURER_PART_NUMBER") "RC0603JR071KL")
        (field (name "NEWARKPARTNUMBER") "14M7231")
        (field (name "COPYRIGHT") "Copyright C 2015 Accelerated Designs. All rights reserved")
      )
      (libsource (lib "eagle-import") (part "RC0603JR-071KLRC0603N-M"))
    )
    (comp (ref "R8")
      (value "10k")
      (footprint "eagle-import:RC0805N")
      (fields
        (field (name "DIGIKEYPARTNUMBER") "P10KDATRND")
        (field (name "MANUFACTURER_PART_NUMBER") "ERA6AEB103V")
        (field (name "TOLERANCE") "0.1%")
        (field (name "COPYRIGHT") "Copyright C 2015 Accelerated Designs. All rights reserved")
      )
      (libsource (lib "eagle-import") (part "Controller Board_178037_ERA-6AEB103V"))
    )
    (comp (ref "R9")
      (value "10k")
      (footprint "eagle-import:RC0805N")
      (fields
        (field (name "DIGIKEYPARTNUMBER") "P10KDATRND")
        (field (name "MANUFACTURER_PART_NUMBER") "ERA6AEB103V")
        (field (name "TOLERANCE") "0.1%")
        (field (name "COPYRIGHT") "Copyright C 2015 Accelerated Designs. All rights reserved")
      )
      (libsource (lib "eagle-import") (part "Controller Board_178037_ERA-6AEB103V"))
    )
    (comp (ref "R10")
      (value "10k")
      (footprint "eagle-import:RC0805N")
      (fields
        (field (name "DIGIKEYPARTNUMBER") "P10KDATRND")
        (field (name "MANUFACTURER_PART_NUMBER") "ERA6AEB103V")
        (field (name "TOLERANCE") "0.1%")
        (field (name "COPYRIGHT") "Copyright C 2015 Accelerated Designs. All rights reserved")
      )
      (libsource (lib "eagle-import") (part "Controller Board_178037_ERA-6AEB103V"))
    )
    (comp (ref "R11")
      (value "20R")
      (footprint "eagle-import:RC0603N-M")
      (fields (field (name "MANUFACTURER_PART_NUMBER") "RC0603JR0720RL"))
      (libsource (lib "eagle-import") (part "RC0603JR-0720RLRC0603N-M"))
    )
    (comp (ref "R12")
      (value "1k")
      (footprint "eagle-import:RC0603N-M")
      (fields
        (field (name "DIGIKEYPARTNUMBER") "3111.0KGRTRND")
        (field (name "MANUFACTURER_PART_NUMBER") "RC0603JR071KL")
        (field (name "NEWARKPARTNUMBER") "14M7231")
        (field (name "COPYRIGHT") "Copyright C 2015 Accelerated Designs. All rights reserved")
      )
      (libsource (lib "eagle-import") (part "RC0603JR-071KLRC0603N-M"))
    )
    (comp (ref "R13")
      (value "1k")
      (footprint "eagle-import:RC0603N-M")
      (fields
        (field (name "DIGIKEYPARTNUMBER") "3111.0KGRTRND")
        (field (name "MANUFACTURER_PART_NUMBER") "RC0603JR071KL")
        (field (name "NEWARKPARTNUMBER") "14M7231")
        (field (name "COPYRIGHT") "Copyright C 2015 Accelerated Designs. All rights reserved")
      )
      (libsource (lib "eagle-import") (part "RC0603JR-071KLRC0603N-M"))
    )
    (comp (ref "R14")
      (value "20R")
      (footprint "eagle-import:RC0603N-M")
      (fields (field (name "MANUFACTURER_PART_NUMBER") "RC0603JR0720RL"))
      (libsource (lib "eagle-import") (part "RC0603JR-0720RLRC0603N-M"))
    )
    (comp (ref "R15")
      (value "20R")
      (footprint "eagle-import:RC0603N-M")
      (fields (field (name "MANUFACTURER_PART_NUMBER") "RC0603JR0720RL"))
      (libsource (lib "eagle-import") (part "RC0603JR-0720RLRC0603N-M"))
    )
    (comp (ref "R16")
      (value "10k")
      (footprint "eagle-import:RC0805N")
      (fields
        (field (name "DIGIKEYPARTNUMBER") "P10KDATRND")
        (field (name "MANUFACTURER_PART_NUMBER") "ERA6AEB103V")
        (field (name "TOLERANCE") "0.1%")
        (field (name "COPYRIGHT") "Copyright C 2015 Accelerated Designs. All rights reserved")
      )
      (libsource (lib "eagle-import") (part "Controller Board_178037_ERA-6AEB103V"))
    )
    (comp (ref "R17")
      (value "20R")
      (footprint "eagle-import:RC0603N-M")
      (fields (field (name "MANUFACTURER_PART_NUMBER") "RC0603JR0720RL"))
      (libsource (lib "eagle-import") (part "RC0603JR-0720RLRC0603N-M"))
    )
    (comp (ref "R18")
      (value "340R")
      (footprint "eagle-import:RC0603N")
      (fields
        (field (name "DIGIKEYPARTNUMBER") "311340HRTRND")
        (field (name "MANUFACTURER_PART_NUMBER") "RC0603FR07340RL")
        (field (name "NEWARKPARTNUMBER") "66R2325")
        (field (name "COPYRIGHT") "Copyright C 2015 Accelerated Designs. All rights reserved")
      )
      (libsource (lib "eagle-import") (part "RC0603FR-07340RL"))
    )
    (comp (ref "R19")
      (value "24.9k")
      (footprint "eagle-import:RC0402N-M")
      (fields (field (name "MANUFACTURER_PART_NUMBER") "RC0402FR0724K9L"))
      (libsource (lib "eagle-import") (part "RC0402FR-0724K9LRC0402N-M"))
    )
    (comp (ref "R20")
      (value "24.9k")
      (footprint "eagle-import:RC0402N-M")
      (fields (field (name "MANUFACTURER_PART_NUMBER") "RC0402FR0724K9L"))
      (libsource (lib "eagle-import") (part "RC0402FR-0724K9LRC0402N-M"))
    )
    (comp (ref "R21")
      (value "20R")
      (footprint "eagle-import:RC0603N-M")
      (fields (field (name "MANUFACTURER_PART_NUMBER") "RC0603JR0720RL"))
      (libsource (lib "eagle-import") (part "RC0603JR-0720RLRC0603N-M"))
    )
    (comp (ref "R23")
      (value "10k")
      (footprint "eagle-import:RC0805N")
      (fields
        (field (name "DIGIKEYPARTNUMBER") "P10KDATRND")
        (field (name "MANUFACTURER_PART_NUMBER") "ERA6AEB103V")
        (field (name "TOLERANCE") "0.1%")
        (field (name "COPYRIGHT") "Copyright C 2015 Accelerated Designs. All rights reserved")
      )
      (libsource (lib "eagle-import") (part "Controller Board_178037_ERA-6AEB103V"))
    )
    (comp (ref "R24")
      (value "10k")
      (footprint "eagle-import:RC0805N")
      (fields
        (field (name "DIGIKEYPARTNUMBER") "P10KDATRND")
        (field (name "MANUFACTURER_PART_NUMBER") "ERA6AEB103V")
        (field (name "TOLERANCE") "0.1%")
        (field (name "COPYRIGHT") "Copyright C 2015 Accelerated Designs. All rights reserved")
      )
      (libsource (lib "eagle-import") (part "Controller Board_178037_ERA-6AEB103V"))
    )
    (comp (ref "R25")
      (value "10k")
      (footprint "eagle-import:RC0805N")
      (fields
        (field (name "DIGIKEYPARTNUMBER") "P10KDATRND")
        (field (name "MANUFACTURER_PART_NUMBER") "ERA6AEB103V")
        (field (name "TOLERANCE") "0.1%")
        (field (name "COPYRIGHT") "Copyright C 2015 Accelerated Designs. All rights reserved")
      )
      (libsource (lib "eagle-import") (part "Controller Board_178037_ERA-6AEB103V"))
    )
    (comp (ref "R26")
      (value "10k")
      (footprint "eagle-import:RC0805N")
      (fields
        (field (name "DIGIKEYPARTNUMBER") "P10KDATRND")
        (field (name "MANUFACTURER_PART_NUMBER") "ERA6AEB103V")
        (field (name "TOLERANCE") "0.1%")
        (field (name "COPYRIGHT") "Copyright C 2015 Accelerated Designs. All rights reserved")
      )
      (libsource (lib "eagle-import") (part "Controller Board_178037_ERA-6AEB103V"))
    )
    (comp (ref "R27")
      (value "10k")
      (footprint "eagle-import:RC0805N")
      (fields
        (field (name "DIGIKEYPARTNUMBER") "P10KDATRND")
        (field (name "MANUFACTURER_PART_NUMBER") "ERA6AEB103V")
        (field (name "TOLERANCE") "0.1%")
        (field (name "COPYRIGHT") "Copyright C 2015 Accelerated Designs. All rights reserved")
      )
      (libsource (lib "eagle-import") (part "Controller Board_178037_ERA-6AEB103V"))
    )
    (comp (ref "R28")
      (value "10k")
      (footprint "eagle-import:RC0805N")
      (fields
        (field (name "DIGIKEYPARTNUMBER") "P10KDATRND")
        (field (name "MANUFACTURER_PART_NUMBER") "ERA6AEB103V")
        (field (name "TOLERANCE") "0.1%")
        (field (name "COPYRIGHT") "Copyright C 2015 Accelerated Designs. All rights reserved")
      )
      (libsource (lib "eagle-import") (part "Controller Board_178037_ERA-6AEB103V"))
    )
    (comp (ref "R29")
      (value "10k")
      (footprint "eagle-import:RC0805N")
      (fields
        (field (name "DIGIKEYPARTNUMBER") "P10KDATRND")
        (field (name "MANUFACTURER_PART_NUMBER") "ERA6AEB103V")
        (field (name "TOLERANCE") "0.1%")
        (field (name "COPYRIGHT") "Copyright C 2015 Accelerated Designs. All rights reserved")
      )
      (libsource (lib "eagle-import") (part "Controller Board_178037_ERA-6AEB103V"))
    )
    (comp (ref "R30")
      (value "20R")
      (footprint "eagle-import:RC0603N-M")
      (fields (field (name "MANUFACTURER_PART_NUMBER") "RC0603JR0720RL"))
      (libsource (lib "eagle-import") (part "RC0603JR-0720RLRC0603N-M"))
    )
    (comp (ref "R31")
      (value "20R")
      (footprint "eagle-import:RC0603N-M")
      (fields (field (name "MANUFACTURER_PART_NUMBER") "RC0603JR0720RL"))
      (libsource (lib "eagle-import") (part "RC0603JR-0720RLRC0603N-M"))
    )
    (comp (ref "R32")
      (value "20R")
      (footprint "eagle-import:RC0603N-M")
      (fields (field (name "MANUFACTURER_PART_NUMBER") "RC0603JR0720RL"))
      (libsource (lib "eagle-import") (part "RC0603JR-0720RLRC0603N-M"))
    )
    (comp (ref "R33")
      (value "340R")
      (footprint "eagle-import:RC0603N")
      (fields
        (field (name "DIGIKEYPARTNUMBER") "311340HRTRND")
        (field (name "MANUFACTURER_PART_NUMBER") "RC0603FR07340RL")
        (field (name "NEWARKPARTNUMBER") "66R2325")
        (field (name "COPYRIGHT") "Copyright C 2015 Accelerated Designs. All rights reserved")
      )
      (libsource (lib "eagle-import") (part "RC0603FR-07340RL"))
    )
    (comp (ref "R38")
      (value "NF")
      (footprint "eagle-import:RC0805N")
      (fields
        (field (name "DIGIKEYPARTNUMBER") "P10KDATRND")
        (field (name "MANUFACTURER_PART_NUMBER") "ERA6AEB103V")
        (field (name "TOLERANCE") "0.1%")
        (field (name "COPYRIGHT") "Copyright C 2015 Accelerated Designs. All rights reserved")
      )
      (libsource (lib "eagle-import") (part "Controller Board_178037_ERA-6AEB103V"))
    )
    (comp (ref "R39")
      (value "100k")
      (footprint "eagle-import:RC0603N-M")
      (fields (field (name "MANUFACTURER_PART_NUMBER") "RC0603JR07100KL"))
      (libsource (lib "eagle-import") (part "RC0603JR-07100KLRC0603N-M"))
    )
    (comp (ref "R40")
      (value "100k")
      (footprint "eagle-import:RC0603N-M")
      (fields (field (name "MANUFACTURER_PART_NUMBER") "RC0603JR07100KL"))
      (libsource (lib "eagle-import") (part "RC0603JR-07100KLRC0603N-M"))
    )
    (comp (ref "R41")
      (value "10k")
      (footprint "eagle-import:RC0805N")
      (fields
        (field (name "DIGIKEYPARTNUMBER") "P10KDATRND")
        (field (name "MANUFACTURER_PART_NUMBER") "ERA6AEB103V")
        (field (name "TOLERANCE") "0.1%")
        (field (name "COPYRIGHT") "Copyright C 2015 Accelerated Designs. All rights reserved")
      )
      (libsource (lib "eagle-import") (part "Controller Board_178037_ERA-6AEB103V"))
    )
    (comp (ref "R42")
      (value "100k")
      (footprint "eagle-import:RC0603N-M")
      (fields (field (name "MANUFACTURER_PART_NUMBER") "RC0603JR07100KL"))
      (libsource (lib "eagle-import") (part "RC0603JR-07100KLRC0603N-M"))
    )
    (comp (ref "R43")
      (value "10k")
      (footprint "eagle-import:RC0805N")
      (fields
        (field (name "DIGIKEYPARTNUMBER") "P10KDATRND")
        (field (name "MANUFACTURER_PART_NUMBER") "ERA6AEB103V")
        (field (name "TOLERANCE") "0.1%")
        (field (name "COPYRIGHT") "Copyright C 2015 Accelerated Designs. All rights reserved")
      )
      (libsource (lib "eagle-import") (part "Controller Board_178037_ERA-6AEB103V"))
    )
    (comp (ref "R45")
      (value "10k")
      (footprint "eagle-import:RC0805N")
      (fields
        (field (name "DIGIKEYPARTNUMBER") "P10KDATRND")
        (field (name "MANUFACTURER_PART_NUMBER") "ERA6AEB103V")
        (field (name "TOLERANCE") "0.1%")
        (field (name "COPYRIGHT") "Copyright C 2015 Accelerated Designs. All rights reserved")
      )
      (libsource (lib "eagle-import") (part "Controller Board_178037_ERA-6AEB103V"))
    )
    (comp (ref "R50")
      (value "12k")
      (footprint "eagle-import:RC0402N-M")
      (fields (field (name "MANUFACTURER_PART_NUMBER") "RC0402FR0712KL"))
      (libsource (lib "eagle-import") (part "RC0402FR-0712KLRC0402N-M"))
    )
    (comp (ref "R51")
      (value "10k")
      (footprint "eagle-import:RC0805N")
      (fields
        (field (name "DIGIKEYPARTNUMBER") "P10KDATRND")
        (field (name "MANUFACTURER_PART_NUMBER") "ERA6AEB103V")
        (field (name "TOLERANCE") "0.1%")
        (field (name "COPYRIGHT") "Copyright C 2015 Accelerated Designs. All rights reserved")
      )
      (libsource (lib "eagle-import") (part "ERA-6AEB103V"))
    )
    (comp (ref "R52")
      (value "12.4k")
      (footprint "eagle-import:YAG_R0402-M")
      (fields (field (name "MANUFACTURER_PART_NUMBER") "RC0402FR0712K4L"))
      (libsource (lib "eagle-import") (part "RC0402FR-0712K4LYAG_R0402-M"))
    )
    (comp (ref "TP1")
      (value "TPB2,54")
      (footprint "eagle-import:B2,54")
      (libsource (lib "eagle-import") (part "TPB2,54"))
    )
    (comp (ref "TP2")
      (value "TPB2,54")
      (footprint "eagle-import:B2,54")
      (libsource (lib "eagle-import") (part "TPB2,54"))
    )
    (comp (ref "TP3")
      (value "TPB2,54")
      (footprint "eagle-import:B2,54")
      (libsource (lib "eagle-import") (part "TPB2,54"))
    )
    (comp (ref "U$2")
      (value "MICROSD")
      (footprint "eagle-import:MICROSD")
      (libsource (lib "eagle-import") (part "MICROSD"))
    )
    (comp (ref "U1")
      (value "AAT3620_BATT_CHARGER")
      (footprint "eagle-import:AAT3620_TDFN")
      (libsource (lib "eagle-import") (part "AAT3620_BATT_CHARGER"))
    )
    (comp (ref "U2")
      (value "8 CH")
      (footprint "eagle-import:21-0055H_16-M")
      (fields
        (field (name "DIGIKEYPARTNUMBER") "MAX11608EEE+ND")
        (field (name "MANUFACTURER_PART_NUMBER") "MAX11608EEE+")
        (field (name "COPYRIGHT") "Copyright C 2015 Accelerated Designs. All rights reserved")
      )
      (libsource (lib "eagle-import") (part "MAX11608EEE+21-0055H_16-M"))
    )
    (comp (ref "U5")
      (value "LAN9512-JZXQFN64_9X9MC-M")
      (footprint "eagle-import:QFN64_9X9MC-M")
      (fields (field (name "MANUFACTURER_PART_NUMBER") "LAN9512JZX"))
      (libsource (lib "eagle-import") (part "LAN9512-JZXQFN64_9X9MC-M"))
    )
    (comp (ref "U6")
      (value "COMPUTE_MODULE")
      (footprint "eagle-import:SO-DIMM")
      (libsource (lib "eagle-import") (part "COMPUTE_MODULE"))
    )
    (comp (ref "U7")
      (value "ESD5384")
      (footprint "eagle-import:WLCSP9")
      (libsource (lib "eagle-import") (part "ESD5384"))
    )
    (comp (ref "U8")
      (value "PEC12R")
      (footprint "eagle-import:PEC12R")
      (libsource (lib "eagle-import") (part "PEC12R"))
    )
    (comp (ref "U9")
      (value "PEC12R")
      (footprint "eagle-import:PEC12R")
      (libsource (lib "eagle-import") (part "PEC12R"))
    )
    (comp (ref "U12")
      (value "APPLE_2.0C_COPROCESSOR")
      (footprint "eagle-import:PG-USON-8-1")
      (libsource (lib "eagle-import") (part "APPLE_2.0C_COPROCESSOR"))
    )
    (comp (ref "U17")
      (value "ATTINY10-TSHR6ST1-M")
      (footprint "eagle-import:6ST1-M")
      (fields (field (name "MANUFACTURER_PART_NUMBER") "ATTINY10TSHR"))
      (libsource (lib "eagle-import") (part "ATTINY10-TSHR6ST1-M"))
    )
    (comp (ref "U18")
      (value "ESP12ESMD")
      (footprint "eagle-import:ESP12E-SMD")
      (libsource (lib "eagle-import") (part "ESP12ESMD"))
    )
    (comp (ref "U19")
      (value "WM8960")
      (footprint "eagle-import:32QFN")
      (libsource (lib "eagle-import") (part "WM8960"))
    )
    (comp (ref "Y1")
      (value "DSC6001")
      (footprint "eagle-import:4-VFLGA")
      (libsource (lib "eagle-import") (part "DSC6001"))
    )
    (comp (ref "C6")
      (value "10nF")
      (footprint "eagle-import:0603_CAPACITOR")
      (libsource (lib "eagle-import") (part "10NF_CAPACITOR"))
    )
    (comp (ref "C7")
      (value "10nF")
      (footprint "eagle-import:0603_CAPACITOR")
      (libsource (lib "eagle-import") (part "10NF_CAPACITOR"))
    )
    (comp (ref "C8")
      (value "10uF")
      (footprint "eagle-import:G-21")
      (fields
        (field (name "MANUFACTURER_PART_NUMBER") "GRM21BR60J106ME19L")
        (field (name "COPYRIGHT") "Copyright C 2015 Accelerated Designs. All rights reserved")
      )
      (libsource (lib "eagle-import") (part "Controller Board_178037_GRM21BR60J106ME19L"))
    )
    (comp (ref "C11")
      (value "10uF")
      (footprint "eagle-import:G-21")
      (fields
        (field (name "MANUFACTURER_PART_NUMBER") "GRM21BR60J106ME19L")
        (field (name "COPYRIGHT") "Copyright C 2015 Accelerated Designs. All rights reserved")
      )
      (libsource (lib "eagle-import") (part "Controller Board_178037_GRM21BR60J106ME19L"))
    )
    (comp (ref "C16")
      (value "22uF")
      (footprint "eagle-import:G-21")
      (fields
        (field (name "MANUFACTURER_PART_NUMBER") "GRM21BR60J226ME39L")
        (field (name "COPYRIGHT") "Copyright C 2015 Accelerated Designs. All rights reserved")
      )
      (libsource (lib "eagle-import") (part "GRM21BR60J226ME39L"))
    )
    (comp (ref "C17")
      (value "10uF")
      (footprint "eagle-import:G-21")
      (fields
        (field (name "MANUFACTURER_PART_NUMBER") "GRM21BR60J106ME19L")
        (field (name "COPYRIGHT") "Copyright C 2015 Accelerated Designs. All rights reserved")
      )
      (libsource (lib "eagle-import") (part "Controller Board_178037_GRM21BR60J106ME19L"))
    )
    (comp (ref "C18")
      (value "560pF")
      (footprint "eagle-import:CC0402N-M")
      (fields (field (name "MANUFACTURER_PART_NUMBER") "CC0402KRX7R9BB561"))
      (libsource (lib "eagle-import") (part "CC0402KRX7R9BB561CC0402N-M"))
    )
    (comp (ref "C33")
      (value "10uF")
      (footprint "eagle-import:G-21")
      (fields
        (field (name "MANUFACTURER_PART_NUMBER") "GRM21BR60J106ME19L")
        (field (name "COPYRIGHT") "Copyright C 2015 Accelerated Designs. All rights reserved")
      )
      (libsource (lib "eagle-import") (part "Controller Board_178037_GRM21BR60J106ME19L"))
    )
    (comp (ref "C34")
      (value "10uF")
      (footprint "eagle-import:G-21")
      (fields
        (field (name "MANUFACTURER_PART_NUMBER") "GRM21BR60J106ME19L")
        (field (name "COPYRIGHT") "Copyright C 2015 Accelerated Designs. All rights reserved")
      )
      (libsource (lib "eagle-import") (part "Controller Board_178037_GRM21BR60J106ME19L"))
    )
    (comp (ref "L1")
      (value "4.7uH")
      (footprint "eagle-import:1008")
      (libsource (lib "eagle-import") (part "DFE252012P-4R7M=P2{dblquote}"))
    )
    (comp (ref "L2")
      (value "470nH")
      (footprint "eagle-import:470NH_INDUCTOR")
      (libsource (lib "eagle-import") (part "470NH_INDUCTOR"))
    )
    (comp (ref "L3")
      (value "470nH")
      (footprint "eagle-import:470NH_INDUCTOR")
      (libsource (lib "eagle-import") (part "470NH_INDUCTOR"))
    )
    (comp (ref "R4")
      (value "10k")
      (footprint "eagle-import:RC0805N")
      (fields
        (field (name "DIGIKEYPARTNUMBER") "P10KDATRND")
        (field (name "MANUFACTURER_PART_NUMBER") "ERA6AEB103V")
        (field (name "TOLERANCE") "0.1%")
        (field (name "COPYRIGHT") "Copyright C 2015 Accelerated Designs. All rights reserved")
      )
      (libsource (lib "eagle-import") (part "Controller Board_178037_ERA-6AEB103V"))
    )
    (comp (ref "R48")
      (value "100k")
      (footprint "eagle-import:RC0603N-M")
      (fields (field (name "MANUFACTURER_PART_NUMBER") "RC0603JR07100KL"))
      (libsource (lib "eagle-import") (part "RC0603JR-07100KLRC0603N-M"))
    )
    (comp (ref "R49")
      (value "100k")
      (footprint "eagle-import:RC0603N-M")
      (fields (field (name "MANUFACTURER_PART_NUMBER") "RC0603JR07100KL"))
      (libsource (lib "eagle-import") (part "RC0603JR-07100KLRC0603N-M"))
    )
    (comp (ref "U3")
      (value "TPS61256YFFR")
      (footprint "eagle-import:YFF9")
      (libsource (lib "eagle-import") (part "TPS61256YFFR"))
    )
    (comp (ref "U10")
      (value "TPS6209")
      (footprint "eagle-import:VQFN16")
      (libsource (lib "eagle-import") (part "TPS6209"))
    )
    (comp (ref "U11")
      (value "LM3880MF-1AA/NOPBMF06A-M")
      (footprint "eagle-import:MF06A-M")
      (fields (field (name "MANUFACTURER_PART_NUMBER") "lm3880mf1aaNOPB"))
      (libsource (lib "eagle-import") (part "LM3880MF-1AA/NOPBMF06A-M"))
    )
    (comp (ref "U16")
      (value "MIC23050")
      (footprint "eagle-import:MLF(ML)_8PIN")
      (libsource (lib "eagle-import") (part "MIC23050"))
    )
  )
  (nets
    (net (code "1") (name "+1V8") (class "Default")
      (node (ref "C17") (pin "2") (pinfunction "2_2") (pintype "passive"))
      (node (ref "C18") (pin "2") (pinfunction "2_2") (pintype "passive"))
      (node (ref "L3") (pin "P$2") (pinfunction "2_P$2") (pintype "passive"))
      (node (ref "R39") (pin "1") (pinfunction "11_1") (pintype "passive"))
      (node (ref "U16") (pin "4") (pinfunction "SNS_4") (pintype "bidirectional"))
      (node (ref "U6") (pin "183") (pinfunction "1V8_183") (pintype "bidirectional"))
      (node (ref "U6") (pin "184") (pinfunction "1V8_184") (pintype "bidirectional"))
      (node (ref "U6") (pin "185") (pinfunction "1V8_185") (pintype "bidirectional"))
      (node (ref "U6") (pin "186") (pinfunction "1V8_186") (pintype "bidirectional"))
    )
    (net (code "2") (name "+3V3") (class "Default")
      (node (ref "C16") (pin "2") (pinfunction "2_2") (pintype "passive"))
      (node (ref "C20") (pin "2") (pinfunction "2_2") (pintype "passive"))
      (node (ref "C21") (pin "2") (pinfunction "2_2") (pintype "passive"))
      (node (ref "C22") (pin "2") (pinfunction "2_2") (pintype "passive"))
      (node (ref "C23") (pin "2") (pinfunction "2_2") (pintype "passive"))
      (node (ref "C35") (pin "2") (pinfunction "2_2") (pintype "passive"))
      (node (ref "C36") (pin "2") (pinfunction "2_2") (pintype "passive"))
      (node (ref "C41") (pin "2") (pinfunction "2_2") (pintype "passive"))
      (node (ref "C60") (pin "2") (pinfunction "2_2") (pintype "passive"))
      (node (ref "C61") (pin "2") (pinfunction "2_2") (pintype "passive"))
      (node (ref "C62") (pin "2") (pinfunction "2_2") (pintype "passive"))
      (node (ref "C63") (pin "2") (pinfunction "2_2") (pintype "passive"))
      (node (ref "C64") (pin "2") (pinfunction "2_2") (pintype "passive"))
      (node (ref "C68") (pin "2") (pinfunction "2_2") (pintype "passive"))
      (node (ref "C9") (pin "2") (pinfunction "2_2") (pintype "passive"))
      (node (ref "D2") (pin "A") (pinfunction "A_A") (pintype "passive"))
      (node (ref "D3") (pin "A") (pinfunction "A_A") (pintype "passive"))
      (node (ref "FB2") (pin "2") (pinfunction "2_2") (pintype "passive"))
      (node (ref "J1") (pin "3") (pinfunction "3_3") (pintype "bidirectional"))
      (node (ref "J10") (pin "2") (pinfunction "2_2") (pintype "bidirectional"))
      (node (ref "J11") (pin "2") (pinfunction "2_2") (pintype "bidirectional"))
      (node (ref "J4") (pin "1") (pinfunction "1_1") (pintype "bidirectional"))
      (node (ref "J5") (pin "11") (pinfunction "11_11") (pintype "bidirectional"))
      (node (ref "J8") (pin "2") (pinfunction "2_2") (pintype "bidirectional"))
      (node (ref "L2") (pin "P$2") (pinfunction "2_P$2") (pintype "passive"))
      (node (ref "R23") (pin "1") (pinfunction "11_1") (pintype "passive"))
      (node (ref "R25") (pin "1") (pinfunction "11_1") (pintype "passive"))
      (node (ref "R26") (pin "1") (pinfunction "11_1") (pintype "passive"))
      (node (ref "R29") (pin "1") (pinfunction "11_1") (pintype "passive"))
      (node (ref "R32") (pin "2") (pinfunction "22_2") (pintype "passive"))
      (node (ref "R38") (pin "1") (pinfunction "11_1") (pintype "passive"))
      (node (ref "R51") (pin "2") (pinfunction "22_2") (pintype "passive"))
      (node (ref "R6") (pin "1") (pinfunction "11_1") (pintype "passive"))
      (node (ref "R7") (pin "1") (pinfunction "11_1") (pintype "passive"))
      (node (ref "U$2") (pin "4") (pinfunction "VDD_4") (pintype "bidirectional"))
      (node (ref "U10") (pin "16") (pinfunction "VOS_16") (pintype "bidirectional"))
      (node (ref "U12") (pin "7") (pinfunction "RST_7") (pintype "bidirectional"))
      (node (ref "U12") (pin "8") (pinfunction "VCC_8") (pintype "bidirectional"))
      (node (ref "U17") (pin "5") (pinfunction "VCC_5") (pintype "power_in"))
      (node (ref "U18") (pin "VCC") (pinfunction "VCC_VCC") (pintype "bidirectional"))
      (node (ref "U19") (pin "10") (pinfunction "DBVDD_10") (pintype "bidirectional"))
      (node (ref "U19") (pin "21") (pinfunction "SPKVDD_21") (pintype "bidirectional"))
      (node (ref "U19") (pin "26") (pinfunction "SPKVDD_26") (pintype "bidirectional"))
      (node (ref "U19") (pin "8") (pinfunction "DCVDD_8") (pintype "bidirectional"))
      (node (ref "U2") (pin "16") (pinfunction "VDD_16") (pintype "power_in"))
      (node (ref "U5") (pin "11") (pinfunction "VBUS_DET_11") (pintype "power_in"))
      (node (ref "U5") (pin "19") (pinfunction "VDD33IO_2_19") (pintype "power_in"))
      (node (ref "U5") (pin "27") (pinfunction "VDD33IO_3_27") (pintype "power_in"))
      (node (ref "U5") (pin "33") (pinfunction "VDD33IO_4_33") (pintype "power_in"))
      (node (ref "U5") (pin "39") (pinfunction "VDD33IO_5_39") (pintype "power_in"))
      (node (ref "U5") (pin "40") (pinfunction "TEST3_40") (pintype "passive"))
      (node (ref "U5") (pin "46") (pinfunction "VDD33IO_46") (pintype "power_in"))
      (node (ref "U6") (pin "189") (pinfunction "VDAC_189") (pintype "bidirectional"))
      (node (ref "U6") (pin "190") (pinfunction "VDAC_190") (pintype "bidirectional"))
      (node (ref "U6") (pin "191") (pinfunction "3V3_191") (pintype "bidirectional"))
      (node (ref "U6") (pin "192") (pinfunction "3V3_192") (pintype "bidirectional"))
      (node (ref "U6") (pin "193") (pinfunction "3V3_193") (pintype "bidirectional"))
      (node (ref "U6") (pin "194") (pinfunction "3V3_194") (pintype "bidirectional"))
      (node (ref "U6") (pin "197") (pinfunction "VBAT_197") (pintype "bidirectional"))
      (node (ref "U6") (pin "198") (pinfunction "VBAT_198") (pintype "bidirectional"))
      (node (ref "U6") (pin "199") (pinfunction "VBAT_199") (pintype "bidirectional"))
      (node (ref "U6") (pin "200") (pinfunction "VBAT_200") (pintype "bidirectional"))
      (node (ref "U6") (pin "39") (pinfunction "GPIO0-27_VDD_39") (pintype "bidirectional"))
      (node (ref "U6") (pin "4") (pinfunction "SDX_VDD_4") (pintype "bidirectional"))
      (node (ref "U6") (pin "40") (pinfunction "GPIO0-27_VDD_40") (pintype "bidirectional"))
      (node (ref "U6") (pin "41") (pinfunction "GPIO28-45_VDD_41") (pintype "bidirectional"))
      (node (ref "U6") (pin "42") (pinfunction "GPIO28-45_VDD_42") (pintype "bidirectional"))
      (node (ref "U6") (pin "6") (pinfunction "SDX_VDD_6") (pintype "bidirectional"))
      (node (ref "Y1") (pin "1") (pinfunction "EN_1") (pintype "bidirectional"))
      (node (ref "Y1") (pin "4") (pinfunction "VDD_4") (pintype "bidirectional"))
    )
    (net (code "3") (name "+5V") (class "Default")
      (node (ref "C33") (pin "2") (pinfunction "2_2") (pintype "passive"))
      (node (ref "J2") (pin "1") (pinfunction "5V_1") (pintype "bidirectional"))
      (node (ref "J2") (pin "2") (pinfunction "5V_2") (pintype "bidirectional"))
      (node (ref "J9") (pin "1") (pinfunction "VCC_1") (pintype "bidirectional"))
      (node (ref "Q6") (pin "G") (pinfunction "G_G") (pintype "passive"))
      (node (ref "U3") (pin "A1") (pinfunction "VOUT_A1") (pintype "output"))
      (node (ref "U3") (pin "A2") (pinfunction "VOUT_A2") (pintype "output"))
      (node (ref "U7") (pin "A1") (pinfunction "5V_A1") (pintype "bidirectional"))
      (node (ref "U7") (pin "B1") (pinfunction "RPU2_B1") (pintype "bidirectional"))
      (node (ref "U7") (pin "C1") (pinfunction "RPU_C1") (pintype "bidirectional"))
    )
    (net (code "4") (name "3.3V_A") (class "Default")
      (node (ref "C19") (pin "2") (pinfunction "2_2") (pintype "passive"))
      (node (ref "C24") (pin "2") (pinfunction "2_2") (pintype "passive"))
      (node (ref "C29") (pin "1") (pinfunction "1_1") (pintype "passive"))
      (node (ref "C37") (pin "1") (pinfunction "1_1") (pintype "passive"))
      (node (ref "C55") (pin "2") (pinfunction "2_2") (pintype "passive"))
      (node (ref "C57") (pin "2") (pinfunction "2_2") (pintype "passive"))
      (node (ref "C58") (pin "2") (pinfunction "2_2") (pintype "passive"))
      (node (ref "C59") (pin "2") (pinfunction "2_2") (pintype "passive"))
      (node (ref "FB2") (pin "1") (pinfunction "1_1") (pintype "passive"))
      (node (ref "J10") (pin "1") (pinfunction "1_1") (pintype "bidirectional"))
      (node (ref "MIC1") (pin "6") (pinfunction "VDD_6") (pintype "bidirectional"))
      (node (ref "MIC2") (pin "6") (pinfunction "VDD_6") (pintype "bidirectional"))
      (node (ref "U19") (pin "32") (pinfunction "AVDD_32") (pintype "bidirectional"))
      (node (ref "U5") (pin "10") (pinfunction "VDD33A_3_10") (pintype "power_in"))
      (node (ref "U5") (pin "49") (pinfunction "VDD33A_4_49") (pintype "power_in"))
      (node (ref "U5") (pin "5") (pinfunction "VDD33A_2_5") (pintype "power_in"))
      (node (ref "U5") (pin "51") (pinfunction "VDD33A_5_51") (pintype "power_in"))
      (node (ref "U5") (pin "54") (pinfunction "VDD33A_6_54") (pintype "power_in"))
      (node (ref "U5") (pin "57") (pinfunction "VDD33A_7_57") (pintype "power_in"))
      (node (ref "U5") (pin "64") (pinfunction "VDD33A_64") (pintype "power_in"))
    )
    (net (code "5") (name "BATT_CNTL") (class "Default")
      (node (ref "Q2") (pin "G") (pinfunction "G_G") (pintype "passive"))
      (node (ref "R10") (pin "1") (pinfunction "11_1") (pintype "passive"))
      (node (ref "TP3") (pin "TP") (pinfunction "TP_TP") (pintype "input"))
      (node (ref "U17") (pin "3") (pinfunction "(PCINT1/TPICLK)_PB1_3") (pintype "bidirectional"))
    )
    (net (code "6") (name "BATT_OUTPUT") (class "Default")
      (node (ref "C11") (pin "2") (pinfunction "2_2") (pintype "passive"))
      (node (ref "C34") (pin "2") (pinfunction "2_2") (pintype "passive"))
      (node (ref "C8") (pin "2") (pinfunction "2_2") (pintype "passive"))
      (node (ref "D6") (pin "C") (pinfunction "12_C") (pintype "passive"))
      (node (ref "L1") (pin "P$2") (pinfunction "2_P$2") (pintype "passive"))
      (node (ref "Q1") (pin "D") (pinfunction "D_D") (pintype "passive"))
      (node (ref "R4") (pin "1") (pinfunction "11_1") (pintype "passive"))
      (node (ref "R48") (pin "1") (pinfunction "11_1") (pintype "passive"))
      (node (ref "R49") (pin "1") (pinfunction "11_1") (pintype "passive"))
      (node (ref "U10") (pin "10") (pinfunction "AVIN_10") (pintype "bidirectional"))
      (node (ref "U10") (pin "11") (pinfunction "PVIN_11") (pintype "bidirectional"))
      (node (ref "U10") (pin "12") (pinfunction "PVIN_12") (pintype "bidirectional"))
      (node (ref "U11") (pin "1") (pinfunction "VCC_1") (pintype "power_in"))
      (node (ref "U16") (pin "7") (pinfunction "VIN_7") (pintype "bidirectional"))
      (node (ref "U3") (pin "A3") (pinfunction "VIN_A3") (pintype "input"))
      (node (ref "U3") (pin "B3") (pinfunction "EN_B3") (pintype "input"))
    )
    (net (code "7") (name "EMMC_DISABLE_N") (class "Default")
      (node (ref "U6") (pin "2") (pinfunction "EMMC_DISABLE_N_2") (pintype "bidirectional"))
    )
    (net (code "8") (name "EMMC_EN_N_1V8") (class "Default")
      (node (ref "U6") (pin "90") (pinfunction "EMMC_EN_N_1V8_90") (pintype "bidirectional"))
    )
    (net (code "9") (name "ENCODER1_A") (class "Default")
      (node (ref "C13") (pin "2") (pinfunction "2_2") (pintype "bidirectional"))
      (node (ref "R42") (pin "1") (pinfunction "11_1") (pintype "passive"))
      (node (ref "R5") (pin "2") (pinfunction "22_2") (pintype "passive"))
      (node (ref "U6") (pin "28") (pinfunction "GPIO28_28") (pintype "bidirectional"))
    )
    (net (code "10") (name "ENCODER1_B") (class "Default")
      (node (ref "C12") (pin "2") (pinfunction "2_2") (pintype "bidirectional"))
      (node (ref "R24") (pin "2") (pinfunction "22_2") (pintype "passive"))
      (node (ref "U6") (pin "5") (pinfunction "GPIO1_5") (pintype "bidirectional"))
    )
    (net (code "11") (name "ENCODER2_A") (class "Default")
      (node (ref "C15") (pin "2") (pinfunction "2_2") (pintype "bidirectional"))
      (node (ref "R27") (pin "2") (pinfunction "22_2") (pintype "passive"))
      (node (ref "U6") (pin "76") (pinfunction "GPIO42_76") (pintype "bidirectional"))
    )
    (net (code "12") (name "ENCODER2_B") (class "Default")
      (node (ref "C14") (pin "2") (pinfunction "2_2") (pintype "bidirectional"))
      (node (ref "R28") (pin "2") (pinfunction "22_2") (pintype "passive"))
      (node (ref "U6") (pin "78") (pinfunction "GPIO43_78") (pintype "bidirectional"))
    )
    (net (code "13") (name "GND") (class "Default")
      (node (ref "C1") (pin "1") (pinfunction "1_1") (pintype "passive"))
      (node (ref "C10") (pin "2") (pinfunction "2_2") (pintype "passive"))
      (node (ref "C11") (pin "1") (pinfunction "1_1") (pintype "passive"))
      (node (ref "C12") (pin "1") (pinfunction "1_1") (pintype "bidirectional"))
      (node (ref "C13") (pin "1") (pinfunction "1_1") (pintype "bidirectional"))
      (node (ref "C14") (pin "1") (pinfunction "1_1") (pintype "bidirectional"))
      (node (ref "C15") (pin "1") (pinfunction "1_1") (pintype "bidirectional"))
      (node (ref "C16") (pin "1") (pinfunction "1_1") (pintype "passive"))
      (node (ref "C17") (pin "1") (pinfunction "1_1") (pintype "passive"))
      (node (ref "C19") (pin "1") (pinfunction "1_1") (pintype "passive"))
      (node (ref "C2") (pin "1") (pinfunction "1_1") (pintype "passive"))
      (node (ref "C20") (pin "1") (pinfunction "1_1") (pintype "passive"))
      (node (ref "C21") (pin "1") (pinfunction "1_1") (pintype "passive"))
      (node (ref "C22") (pin "1") (pinfunction "1_1") (pintype "passive"))
      (node (ref "C23") (pin "1") (pinfunction "1_1") (pintype "passive"))
      (node (ref "C24") (pin "1") (pinfunction "1_1") (pintype "passive"))
      (node (ref "C25") (pin "2") (pinfunction "2_2") (pintype "passive"))
      (node (ref "C26") (pin "2") (pinfunction "2_2") (pintype "passive"))
      (node (ref "C27") (pin "1") (pinfunction "11_1") (pintype "passive"))
      (node (ref "C28") (pin "1") (pinfunction "11_1") (pintype "passive"))
      (node (ref "C29") (pin "2") (pinfunction "2_2") (pintype "passive"))
      (node (ref "C3") (pin "1") (pinfunction "1_1") (pintype "passive"))
      (node (ref "C31") (pin "1") (pinfunction "11_1") (pintype "passive"))
      (node (ref "C32") (pin "1") (pinfunction "11_1") (pintype "passive"))
      (node (ref "C33") (pin "1") (pinfunction "1_1") (pintype "passive"))
      (node (ref "C34") (pin "1") (pinfunction "1_1") (pintype "passive"))
      (node (ref "C35") (pin "1") (pinfunction "1_1") (pintype "passive"))
      (node (ref "C36") (pin "1") (pinfunction "1_1") (pintype "passive"))
      (node (ref "C37") (pin "2") (pinfunction "2_2") (pintype "passive"))
      (node (ref "C39") (pin "1") (pinfunction "11_1") (pintype "passive"))
      (node (ref "C4") (pin "1") (pinfunction "1_1") (pintype "passive"))
      (node (ref "C40") (pin "1") (pinfunction "11_1") (pintype "passive"))
      (node (ref "C41") (pin "1") (pinfunction "1_1") (pintype "passive"))
      (node (ref "C5") (pin "1") (pinfunction "1_1") (pintype "passive"))
      (node (ref "C53") (pin "1") (pinfunction "11_1") (pintype "passive"))
      (node (ref "C54") (pin "1") (pinfunction "1_1") (pintype "passive"))
      (node (ref "C55") (pin "1") (pinfunction "1_1") (pintype "passive"))
      (node (ref "C57") (pin "1") (pinfunction "1_1") (pintype "passive"))
      (node (ref "C58") (pin "1") (pinfunction "1_1") (pintype "passive"))
      (node (ref "C59") (pin "1") (pinfunction "1_1") (pintype "passive"))
      (node (ref "C60") (pin "1") (pinfunction "1_1") (pintype "passive"))
      (node (ref "C61") (pin "1") (pinfunction "1_1") (pintype "passive"))
      (node (ref "C62") (pin "1") (pinfunction "1_1") (pintype "passive"))
      (node (ref "C63") (pin "1") (pinfunction "1_1") (pintype "passive"))
      (node (ref "C64") (pin "1") (pinfunction "1_1") (pintype "passive"))
      (node (ref "C65") (pin "1") (pinfunction "1_1") (pintype "passive"))
      (node (ref "C66") (pin "1") (pinfunction "1_1") (pintype "passive"))
      (node (ref "C67") (pin "1") (pinfunction "1_1") (pintype "passive"))
      (node (ref "C68") (pin "1") (pinfunction "1_1") (pintype "passive"))
      (node (ref "C7") (pin "1") (pinfunction "1_1") (pintype "bidirectional"))
      (node (ref "C8") (pin "1") (pinfunction "1_1") (pintype "passive"))
      (node (ref "C9") (pin "1") (pinfunction "1_1") (pintype "passive"))
      (node (ref "D1") (pin "C") (pinfunction "C_C") (pintype "passive"))
      (node (ref "D4") (pin "C") (pinfunction "C_C") (pintype "passive"))
      (node (ref "J1") (pin "4") (pinfunction "4_4") (pintype "bidirectional"))
      (node (ref "J10") (pin "11") (pinfunction "11_11") (pintype "bidirectional"))
      (node (ref "J10") (pin "14") (pinfunction "14_14") (pintype "bidirectional"))
      (node (ref "J10") (pin "17") (pinfunction "17_17") (pintype "bidirectional"))
      (node (ref "J11") (pin "1") (pinfunction "1_1") (pintype "bidirectional"))
      (node (ref "J2") (pin "3") (pinfunction "GND_3") (pintype "bidirectional"))
      (node (ref "J2") (pin "7") (pinfunction "GND_7") (pintype "bidirectional"))
      (node (ref "J3") (pin "4") (pinfunction "ID_4") (pintype "bidirectional"))
      (node (ref "J3") (pin "5") (pinfunction "GND_5") (pintype "power_in"))
      (node (ref "J3") (pin "6") (pinfunction "GND_6") (pintype "power_in"))
      (node (ref "J3") (pin "7") (pinfunction "GND_7") (pintype "power_in"))
      (node (ref "J3") (pin "P$1") (pinfunction "GND_P$1") (pintype "power_in"))
      (node (ref "J3") (pin "P$2") (pinfunction "GND_P$2") (pintype "power_in"))
      (node (ref "J3") (pin "P$3") (pinfunction "GND_P$3") (pintype "power_in"))
      (node (ref "J3") (pin "P$4") (pinfunction "GND_P$4") (pintype "power_in"))
      (node (ref "J4") (pin "4") (pinfunction "4_4") (pintype "bidirectional"))
      (node (ref "J5") (pin "15") (pinfunction "15_15") (pintype "bidirectional"))
      (node (ref "J6") (pin "2") (pinfunction "GND_2") (pintype "power_in"))
      (node (ref "J7") (pin "11") (pinfunction "GND_11") (pintype "bidirectional"))
      (node (ref "J7") (pin "17") (pinfunction "GND_17") (pintype "bidirectional"))
      (node (ref "J7") (pin "2") (pinfunction "GND_2") (pintype "bidirectional"))
      (node (ref "J7") (pin "5") (pinfunction "GND_5") (pintype "bidirectional"))
      (node (ref "J7") (pin "8") (pinfunction "GND_8") (pintype "bidirectional"))
      (node (ref "J7") (pin "P$1") (pinfunction "GND_P$1") (pintype "bidirectional"))
      (node (ref "J7") (pin "P$2") (pinfunction "GND_P$2") (pintype "bidirectional"))
      (node (ref "J7") (pin "P$3") (pinfunction "GND_P$3") (pintype "bidirectional"))
      (node (ref "J7") (pin "P$4") (pinfunction "GND_P$4") (pintype "bidirectional"))
      (node (ref "J9") (pin "4") (pinfunction "GND_4") (pintype "bidirectional"))
      (node (ref "J9") (pin "5") (pinfunction "GND_5") (pintype "bidirectional"))
      (node (ref "J9") (pin "6") (pinfunction "GND_6") (pintype "bidirectional"))
      (node (ref "MIC1") (pin "1") (pinfunction "GND_1") (pintype "bidirectional"))
      (node (ref "MIC1") (pin "2") (pinfunction "GND_2") (pintype "bidirectional"))
      (node (ref "MIC1") (pin "3") (pinfunction "GND_3") (pintype "bidirectional"))
      (node (ref "MIC1") (pin "5") (pinfunction "GND_5") (pintype "bidirectional"))
      (node (ref "MIC2") (pin "1") (pinfunction "GND_1") (pintype "bidirectional"))
      (node (ref "MIC2") (pin "2") (pinfunction "GND_2") (pintype "bidirectional"))
      (node (ref "MIC2") (pin "3") (pinfunction "GND_3") (pintype "bidirectional"))
      (node (ref "MIC2") (pin "5") (pinfunction "GND_5") (pintype "bidirectional"))
      (node (ref "Q2") (pin "S") (pinfunction "S_S") (pintype "passive"))
      (node (ref "Q5") (pin "S") (pinfunction "S_S") (pintype "passive"))
      (node (ref "R10") (pin "2") (pinfunction "22_2") (pintype "passive"))
      (node (ref "R16") (pin "2") (pinfunction "22_2") (pintype "passive"))
      (node (ref "R19") (pin "1") (pinfunction "11_1") (pintype "passive"))
      (node (ref "R20") (pin "1") (pinfunction "11_1") (pintype "passive"))
      (node (ref "R3") (pin "1") (pinfunction "11_1") (pintype "passive"))
      (node (ref "R40") (pin "2") (pinfunction "22_2") (pintype "passive"))
      (node (ref "R41") (pin "2") (pinfunction "22_2") (pintype "passive"))
      (node (ref "R42") (pin "2") (pinfunction "22_2") (pintype "passive"))
      (node (ref "R43") (pin "2") (pinfunction "22_2") (pintype "passive"))
      (node (ref "R45") (pin "2") (pinfunction "22_2") (pintype "passive"))
      (node (ref "R50") (pin "2") (pinfunction "22_2") (pintype "passive"))
      (node (ref "R52") (pin "1") (pinfunction "11_1") (pintype "passive"))
      (node (ref "U$2") (pin "10") (pinfunction "VSS_10") (pintype "bidirectional"))
      (node (ref "U$2") (pin "11") (pinfunction "VSS_11") (pintype "bidirectional"))
      (node (ref "U$2") (pin "12") (pinfunction "VSS_12") (pintype "bidirectional"))
      (node (ref "U$2") (pin "13") (pinfunction "VSS_13") (pintype "bidirectional"))
      (node (ref "U$2") (pin "6") (pinfunction "VSS_6") (pintype "bidirectional"))
      (node (ref "U$2") (pin "9") (pinfunction "VSS_9") (pintype "bidirectional"))
      (node (ref "U1") (pin "2") (pinfunction "PGND_2") (pintype "power_in"))
      (node (ref "U1") (pin "3") (pinfunction "GND_3") (pintype "power_in"))
      (node (ref "U1") (pin "EP") (pinfunction "EP_EP") (pintype "power_in"))
      (node (ref "U10") (pin "14") (pinfunction "PGND_14") (pintype "bidirectional"))
      (node (ref "U10") (pin "15") (pinfunction "PGND_15") (pintype "bidirectional"))
      (node (ref "U10") (pin "17") (pinfunction "PGND_17") (pintype "bidirectional"))
      (node (ref "U10") (pin "3") (pinfunction "FREQ_3") (pintype "bidirectional"))
      (node (ref "U10") (pin "5") (pinfunction "FB_5") (pintype "bidirectional"))
      (node (ref "U10") (pin "6") (pinfunction "AGND_6") (pintype "bidirectional"))
      (node (ref "U11") (pin "2") (pinfunction "GND_2") (pintype "power_in"))
      (node (ref "U12") (pin "1") (pinfunction "GND_1") (pintype "bidirectional"))
      (node (ref "U12") (pin "9") (pinfunction "GND_9") (pintype "bidirectional"))
      (node (ref "U16") (pin "6") (pinfunction "AGND_6") (pintype "bidirectional"))
      (node (ref "U16") (pin "8") (pinfunction "PGND_8") (pintype "bidirectional"))
      (node (ref "U16") (pin "EP") (pinfunction "PGND_EP") (pintype "bidirectional"))
      (node (ref "U17") (pin "2") (pinfunction "GND_2") (pintype "power_in"))
      (node (ref "U18") (pin "GND") (pinfunction "GND_GND") (pintype "bidirectional"))
      (node (ref "U19") (pin "20") (pinfunction "SPKGND_20") (pintype "bidirectional"))
      (node (ref "U19") (pin "24") (pinfunction "SPKGND_24") (pintype "bidirectional"))
      (node (ref "U19") (pin "28") (pinfunction "AGND_28") (pintype "bidirectional"))
      (node (ref "U19") (pin "9") (pinfunction "DGND_9") (pintype "bidirectional"))
      (node (ref "U19") (pin "EP") (pinfunction "GNDPADDLE_EP") (pintype "bidirectional"))
      (node (ref "U2") (pin "15") (pinfunction "GND_15") (pintype "power_in"))
      (node (ref "U3") (pin "C1") (pinfunction "GND_C1") (pintype "power_in"))
      (node (ref "U3") (pin "C2") (pinfunction "GND_C2") (pintype "power_in"))
      (node (ref "U5") (pin "34") (pinfunction "TEST2_34") (pintype "passive"))
      (node (ref "U5") (pin "44") (pinfunction "CLK24_EN_44") (pintype "input"))
      (node (ref "U5") (pin "65") (pinfunction "EPAD_65") (pintype "passive"))
      (node (ref "U6") (pin "1") (pinfunction "GND_1") (pintype "bidirectional"))
      (node (ref "U6") (pin "103") (pinfunction "GND_103") (pintype "bidirectional"))
      (node (ref "U6") (pin "104") (pinfunction "GND_104") (pintype "bidirectional"))
      (node (ref "U6") (pin "109") (pinfunction "GND_109") (pintype "bidirectional"))
      (node (ref "U6") (pin "110") (pinfunction "GND_110") (pintype "bidirectional"))
      (node (ref "U6") (pin "115") (pinfunction "GND_115") (pintype "bidirectional"))
      (node (ref "U6") (pin "116") (pinfunction "GND_116") (pintype "bidirectional"))
      (node (ref "U6") (pin "121") (pinfunction "GND_121") (pintype "bidirectional"))
      (node (ref "U6") (pin "122") (pinfunction "GND_122") (pintype "bidirectional"))
      (node (ref "U6") (pin "127") (pinfunction "GND_127") (pintype "bidirectional"))
      (node (ref "U6") (pin "13") (pinfunction "GND_13") (pintype "bidirectional"))
      (node (ref "U6") (pin "133") (pinfunction "GND_133") (pintype "bidirectional"))
      (node (ref "U6") (pin "134") (pinfunction "GND_134") (pintype "bidirectional"))
      (node (ref "U6") (pin "139") (pinfunction "GND_139") (pintype "bidirectional"))
      (node (ref "U6") (pin "14") (pinfunction "GND_14") (pintype "bidirectional"))
      (node (ref "U6") (pin "140") (pinfunction "GND_140") (pintype "bidirectional"))
      (node (ref "U6") (pin "145") (pinfunction "GND_145") (pintype "bidirectional"))
      (node (ref "U6") (pin "146") (pinfunction "GND_146") (pintype "bidirectional"))
      (node (ref "U6") (pin "151") (pinfunction "GND_151") (pintype "bidirectional"))
      (node (ref "U6") (pin "152") (pinfunction "GND_152") (pintype "bidirectional"))
      (node (ref "U6") (pin "157") (pinfunction "GND_157") (pintype "bidirectional"))
      (node (ref "U6") (pin "163") (pinfunction "GND_163") (pintype "bidirectional"))
      (node (ref "U6") (pin "164") (pinfunction "GND_164") (pintype "bidirectional"))
      (node (ref "U6") (pin "169") (pinfunction "GND_169") (pintype "bidirectional"))
      (node (ref "U6") (pin "170") (pinfunction "GND_170") (pintype "bidirectional"))
      (node (ref "U6") (pin "181") (pinfunction "GND_181") (pintype "bidirectional"))
      (node (ref "U6") (pin "182") (pinfunction "GND_182") (pintype "bidirectional"))
      (node (ref "U6") (pin "187") (pinfunction "GND_187") (pintype "bidirectional"))
      (node (ref "U6") (pin "188") (pinfunction "GND_188") (pintype "bidirectional"))
      (node (ref "U6") (pin "19") (pinfunction "GND_19") (pintype "bidirectional"))
      (node (ref "U6") (pin "195") (pinfunction "GND_195") (pintype "bidirectional"))
      (node (ref "U6") (pin "196") (pinfunction "GND_196") (pintype "bidirectional"))
      (node (ref "U6") (pin "20") (pinfunction "GND_20") (pintype "bidirectional"))
      (node (ref "U6") (pin "25") (pinfunction "GND_25") (pintype "bidirectional"))
      (node (ref "U6") (pin "26") (pinfunction "GND_26") (pintype "bidirectional"))
      (node (ref "U6") (pin "31") (pinfunction "GND_31") (pintype "bidirectional"))
      (node (ref "U6") (pin "32") (pinfunction "GND_32") (pintype "bidirectional"))
      (node (ref "U6") (pin "37") (pinfunction "GND_37") (pintype "bidirectional"))
      (node (ref "U6") (pin "38") (pinfunction "GND_38") (pintype "bidirectional"))
      (node (ref "U6") (pin "43") (pinfunction "GND_43") (pintype "bidirectional"))
      (node (ref "U6") (pin "44") (pinfunction "GND_44") (pintype "bidirectional"))
      (node (ref "U6") (pin "49") (pinfunction "GND_49") (pintype "bidirectional"))
      (node (ref "U6") (pin "50") (pinfunction "GND_50") (pintype "bidirectional"))
      (node (ref "U6") (pin "55") (pinfunction "GND_55") (pintype "bidirectional"))
      (node (ref "U6") (pin "56") (pinfunction "GND_56") (pintype "bidirectional"))
      (node (ref "U6") (pin "61") (pinfunction "GND_61") (pintype "bidirectional"))
      (node (ref "U6") (pin "62") (pinfunction "GND_62") (pintype "bidirectional"))
      (node (ref "U6") (pin "67") (pinfunction "GND_67") (pintype "bidirectional"))
      (node (ref "U6") (pin "68") (pinfunction "GND_68") (pintype "bidirectional"))
      (node (ref "U6") (pin "7") (pinfunction "GND_7") (pintype "bidirectional"))
      (node (ref "U6") (pin "73") (pinfunction "GND_73") (pintype "bidirectional"))
      (node (ref "U6") (pin "74") (pinfunction "GND_74") (pintype "bidirectional"))
      (node (ref "U6") (pin "79") (pinfunction "GND_79") (pintype "bidirectional"))
      (node (ref "U6") (pin "8") (pinfunction "GND_8") (pintype "bidirectional"))
      (node (ref "U6") (pin "80") (pinfunction "GND_80") (pintype "bidirectional"))
      (node (ref "U6") (pin "85") (pinfunction "GND_85") (pintype "bidirectional"))
      (node (ref "U6") (pin "86") (pinfunction "GND_86") (pintype "bidirectional"))
      (node (ref "U6") (pin "91") (pinfunction "GND_91") (pintype "bidirectional"))
      (node (ref "U6") (pin "92") (pinfunction "GND_92") (pintype "bidirectional"))
      (node (ref "U6") (pin "97") (pinfunction "GND_97") (pintype "bidirectional"))
      (node (ref "U6") (pin "98") (pinfunction "GND_98") (pintype "bidirectional"))
      (node (ref "U6") (pin "G1") (pinfunction "G1_G1") (pintype "bidirectional"))
      (node (ref "U6") (pin "G2") (pinfunction "G2_G2") (pintype "bidirectional"))
      (node (ref "U7") (pin "B2") (pinfunction "GND_B2") (pintype "bidirectional"))
      (node (ref "U7") (pin "C2") (pinfunction "GND_C2") (pintype "bidirectional"))
      (node (ref "U8") (pin "C") (pinfunction "C_C") (pintype "bidirectional"))
      (node (ref "U9") (pin "C") (pinfunction "C_C") (pintype "bidirectional"))
      (node (ref "Y1") (pin "2") (pinfunction "GND_2") (pintype "bidirectional"))
    )
    (net (code "14") (name "GPCLK1") (class "Default")
      (node (ref "R40") (pin "1") (pinfunction "11_1") (pintype "passive"))
      (node (ref "U5") (pin "61") (pinfunction "XI_61") (pintype "input"))
      (node (ref "U6") (pin "82") (pinfunction "GPIO44_82") (pintype "bidirectional"))
    )
    (net (code "15") (name "GPIO36") (class "Default")
      (node (ref "U6") (pin "58") (pinfunction "GPIO36_58") (pintype "bidirectional"))
    )
    (net (code "16") (name "GPIO37") (class "Default")
      (node (ref "U6") (pin "60") (pinfunction "GPIO37_60") (pintype "bidirectional"))
    )
    (net (code "17") (name "HDMI_CEC") (class "Default")
      (node (ref "Q6") (pin "S") (pinfunction "S_S") (pintype "passive"))
      (node (ref "R38") (pin "2") (pinfunction "22_2") (pintype "passive"))
      (node (ref "U6") (pin "171") (pinfunction "HDMI_CEC_171") (pintype "bidirectional"))
    )
    (net (code "18") (name "HDMI_CK_N") (class "Default")
      (node (ref "J7") (pin "12") (pinfunction "CLK_N_12") (pintype "bidirectional"))
      (node (ref "U6") (pin "111") (pinfunction "HDMI_CK_N_111") (pintype "bidirectional"))
    )
    (net (code "19") (name "HDMI_CK_P") (class "Default")
      (node (ref "J7") (pin "10") (pinfunction "CLK_P_10") (pintype "bidirectional"))
      (node (ref "U6") (pin "113") (pinfunction "HDMI_CK_P_113") (pintype "bidirectional"))
    )
    (net (code "20") (name "HDMI_D0_N") (class "Default")
      (node (ref "J7") (pin "9") (pinfunction "TX0_N_9") (pintype "bidirectional"))
      (node (ref "U6") (pin "117") (pinfunction "HDMI_D0_N_117") (pintype "bidirectional"))
    )
    (net (code "21") (name "HDMI_D0_P") (class "Default")
      (node (ref "J7") (pin "7") (pinfunction "TX0_P_7") (pintype "bidirectional"))
      (node (ref "U6") (pin "119") (pinfunction "HDMI_D0_P_119") (pintype "bidirectional"))
    )
    (net (code "22") (name "HDMI_D1_N") (class "Default")
      (node (ref "J7") (pin "6") (pinfunction "TX1_N_6") (pintype "bidirectional"))
      (node (ref "U6") (pin "123") (pinfunction "HDMI_D1_N_123") (pintype "bidirectional"))
    )
    (net (code "23") (name "HDMI_D1_P") (class "Default")
      (node (ref "J7") (pin "4") (pinfunction "TX1_P_4") (pintype "bidirectional"))
      (node (ref "U6") (pin "125") (pinfunction "HDMI_D1_P_125") (pintype "bidirectional"))
    )
    (net (code "24") (name "HDMI_D2_N") (class "Default")
      (node (ref "J7") (pin "3") (pinfunction "TX2_N_3") (pintype "bidirectional"))
      (node (ref "U6") (pin "129") (pinfunction "HDMI_D2_N_129") (pintype "bidirectional"))
    )
    (net (code "25") (name "HDMI_D2_P") (class "Default")
      (node (ref "J7") (pin "1") (pinfunction "TX2_P_1") (pintype "bidirectional"))
      (node (ref "U6") (pin "131") (pinfunction "HDMI_D2_P_131") (pintype "bidirectional"))
    )
    (net (code "26") (name "HDMI_HPD_N_1V8") (class "Default")
      (node (ref "Q5") (pin "D") (pinfunction "D_D") (pintype "passive"))
      (node (ref "R39") (pin "2") (pinfunction "22_2") (pintype "passive"))
      (node (ref "U6") (pin "88") (pinfunction "HDMI_HPD_N_1V8_88") (pintype "bidirectional"))
    )
    (net (code "27") (name "HDMI_SCL") (class "Default")
      (node (ref "J7") (pin "15") (pinfunction "SCL_15") (pintype "bidirectional"))
      (node (ref "U6") (pin "175") (pinfunction "HDMI_SCL_175") (pintype "bidirectional"))
      (node (ref "U7") (pin "A3") (pinfunction "SCL_A3") (pintype "bidirectional"))
    )
    (net (code "28") (name "HDMI_SDA") (class "Default")
      (node (ref "J7") (pin "16") (pinfunction "SDA_16") (pintype "bidirectional"))
      (node (ref "U6") (pin "173") (pinfunction "HDMI_SDA_173") (pintype "bidirectional"))
      (node (ref "U7") (pin "B3") (pinfunction "SDA_B3") (pintype "bidirectional"))
    )
    (net (code "29") (name "I2C_SCL") (class "Default")
      (node (ref "J11") (pin "4") (pinfunction "4_4") (pintype "bidirectional"))
      (node (ref "R6") (pin "2") (pinfunction "22_2") (pintype "passive"))
      (node (ref "U12") (pin "6") (pinfunction "SCL_6") (pintype "bidirectional"))
      (node (ref "U19") (pin "17") (pinfunction "SCLK_17") (pintype "bidirectional"))
      (node (ref "U2") (pin "13") (pinfunction "SCL_13") (pintype "input"))
      (node (ref "U6") (pin "11") (pinfunction "GPIO3_11") (pintype "bidirectional"))
    )
    (net (code "30") (name "I2C_SDA") (class "Default")
      (node (ref "J11") (pin "3") (pinfunction "3_3") (pintype "bidirectional"))
      (node (ref "R7") (pin "2") (pinfunction "22_2") (pintype "passive"))
      (node (ref "U12") (pin "2") (pinfunction "SDA_2") (pintype "bidirectional"))
      (node (ref "U19") (pin "18") (pinfunction "SDIN_18") (pintype "bidirectional"))
      (node (ref "U2") (pin "14") (pinfunction "SDA_14") (pintype "bidirectional"))
      (node (ref "U6") (pin "9") (pinfunction "GPIO2_9") (pintype "bidirectional"))
    )
    (net (code "31") (name "I2S_ADC") (class "Default")
      (node (ref "U19") (pin "16") (pinfunction "ADCDAT_16") (pintype "bidirectional"))
      (node (ref "U6") (pin "69") (pinfunction "GPIO20_69") (pintype "bidirectional"))
    )
    (net (code "32") (name "I2S_CLK") (class "Default")
      (node (ref "U19") (pin "12") (pinfunction "BCLK_12") (pintype "bidirectional"))
      (node (ref "U6") (pin "63") (pinfunction "GPIO18_63") (pintype "bidirectional"))
    )
    (net (code "33") (name "I2S_DAC") (class "Default")
      (node (ref "U19") (pin "14") (pinfunction "DACDAT_14") (pintype "bidirectional"))
      (node (ref "U6") (pin "71") (pinfunction "GPIO21_71") (pintype "bidirectional"))
    )
    (net (code "34") (name "I2S_LRCLK") (class "Default")
      (node (ref "U19") (pin "13") (pinfunction "DACLRC_13") (pintype "bidirectional"))
      (node (ref "U19") (pin "15") (pinfunction "ADCLRC/GPIO_15") (pintype "bidirectional"))
      (node (ref "U6") (pin "65") (pinfunction "GPIO19_65") (pintype "bidirectional"))
    )
    (net (code "35") (name "ID_SD") (class "Default")
      (node (ref "U18") (pin "CH_PD") (pinfunction "CH_PD_CH_PD") (pintype "bidirectional"))
      (node (ref "U6") (pin "3") (pinfunction "GPIO0_3") (pintype "bidirectional"))
    )
    (net (code "36") (name "IRQ") (class "Default")
      (node (ref "J2") (pin "4") (pinfunction "GPIO25_4") (pintype "bidirectional"))
      (node (ref "U6") (pin "70") (pinfunction "GPIO40_70") (pintype "bidirectional"))
    )
    (net (code "37") (name "ISET") (class "Default")
      (node (ref "JP2") (pin "2") (pinfunction "2_2") (pintype "passive"))
      (node (ref "U1") (pin "6") (pinfunction "ISET_6") (pintype "bidirectional"))
    )
    (net (code "38") (name "ITERM") (class "Default")
      (node (ref "R20") (pin "2") (pinfunction "22_2") (pintype "passive"))
      (node (ref "U1") (pin "10") (pinfunction "ITERM_10") (pintype "bidirectional"))
      (node (ref "U2") (pin "11") (pinfunction "AIN6_11") (pintype "input"))
    )
    (net (code "39") (name "J1_SW") (class "Default")
      (node (ref "J5") (pin "12") (pinfunction "12_12") (pintype "bidirectional"))
      (node (ref "U6") (pin "64") (pinfunction "GPIO38_64") (pintype "bidirectional"))
    )
    (net (code "40") (name "J2_SW") (class "Default")
      (node (ref "J10") (pin "18") (pinfunction "18_18") (pintype "bidirectional"))
      (node (ref "U6") (pin "66") (pinfunction "GPIO39_66") (pintype "bidirectional"))
    )
    (net (code "41") (name "LIN1") (class "Default")
      (node (ref "C38") (pin "2") (pinfunction "22_2") (pintype "passive"))
      (node (ref "U19") (pin "4") (pinfunction "LIN1_4") (pintype "bidirectional"))
    )
    (net (code "42") (name "MCLK") (class "Default")
      (node (ref "U19") (pin "11") (pinfunction "MCLK_11") (pintype "bidirectional"))
      (node (ref "Y1") (pin "3") (pinfunction "OUT_3") (pintype "bidirectional"))
    )
    (net (code "43") (name "MIC_OUTPUT") (class "Default")
      (node (ref "U2") (pin "10") (pinfunction "AIN5_10") (pintype "input"))
    )
    (net (code "44") (name "Net-(C27-22)") (class "Default")
      (node (ref "C27") (pin "2") (pinfunction "22_2") (pintype "passive"))
      (node (ref "FB5") (pin "2") (pinfunction "2_2") (pintype "passive"))
      (node (ref "MIC1") (pin "4") (pinfunction "OUT_4") (pintype "bidirectional"))
    )
    (net (code "45") (name "Net-(C28-22)") (class "Default")
      (node (ref "C28") (pin "2") (pinfunction "22_2") (pintype "passive"))
      (node (ref "C30") (pin "1") (pinfunction "11_1") (pintype "passive"))
      (node (ref "FB5") (pin "1") (pinfunction "1_1") (pintype "passive"))
    )
    (net (code "46") (name "Net-(C31-22)") (class "Default")
      (node (ref "C31") (pin "2") (pinfunction "22_2") (pintype "passive"))
      (node (ref "FB6") (pin "2") (pinfunction "2_2") (pintype "passive"))
      (node (ref "MIC2") (pin "4") (pinfunction "OUT_4") (pintype "bidirectional"))
    )
    (net (code "47") (name "Net-(C32-22)") (class "Default")
      (node (ref "C32") (pin "2") (pinfunction "22_2") (pintype "passive"))
      (node (ref "C38") (pin "1") (pinfunction "11_1") (pintype "passive"))
      (node (ref "FB6") (pin "1") (pinfunction "1_1") (pintype "passive"))
    )
    (net (code "48") (name "Net-(C39-22)") (class "Default")
      (node (ref "C39") (pin "2") (pinfunction "22_2") (pintype "passive"))
      (node (ref "FB3") (pin "2") (pinfunction "2_2") (pintype "passive"))
      (node (ref "LS1") (pin "1") (pinfunction "1_1") (pintype "passive"))
    )
    (net (code "49") (name "Net-(C40-22)") (class "Default")
      (node (ref "C40") (pin "2") (pinfunction "22_2") (pintype "passive"))
      (node (ref "FB4") (pin "2") (pinfunction "2_2") (pintype "passive"))
      (node (ref "LS1") (pin "2") (pinfunction "2_2") (pintype "passive"))
    )
    (net (code "50") (name "Net-(C53-22)") (class "Default")
      (node (ref "C53") (pin "2") (pinfunction "22_2") (pintype "passive"))
      (node (ref "FB1") (pin "2") (pinfunction "2_2") (pintype "passive"))
      (node (ref "U5") (pin "62") (pinfunction "VDD18USBPLL_62") (pintype "power_in"))
    )
    (net (code "51") (name "Net-(J3-VCC)") (class "Default")
      (node (ref "C1") (pin "2") (pinfunction "2_2") (pintype "passive"))
      (node (ref "C4") (pin "2") (pinfunction "2_2") (pintype "passive"))
      (node (ref "J3") (pin "1") (pinfunction "VCC_1") (pintype "power_in"))
      (node (ref "R1") (pin "2") (pinfunction "22_2") (pintype "passive"))
      (node (ref "R33") (pin "2") (pinfunction "22_2") (pintype "passive"))
      (node (ref "R41") (pin "1") (pinfunction "11_1") (pintype "passive"))
      (node (ref "U1") (pin "1") (pinfunction "VPIN_1") (pintype "power_in"))
    )
    (net (code "52") (name "Net-(J7-CEC_DAT)") (class "Default")
      (node (ref "J7") (pin "13") (pinfunction "CEC_DAT_13") (pintype "bidirectional"))
      (node (ref "Q6") (pin "D") (pinfunction "D_D") (pintype "passive"))
      (node (ref "U7") (pin "A2") (pinfunction "CEC_A2") (pintype "bidirectional"))
    )
    (net (code "53") (name "Net-(J7-HPD)") (class "Default")
      (node (ref "J7") (pin "19") (pinfunction "HPD_19") (pintype "bidirectional"))
      (node (ref "Q5") (pin "G") (pinfunction "G_G") (pintype "passive"))
      (node (ref "U7") (pin "C3") (pinfunction "HPD_C3") (pintype "bidirectional"))
    )
    (net (code "54") (name "Net-(L1-1)") (class "Default")
      (node (ref "L1") (pin "P$1") (pinfunction "1_P$1") (pintype "passive"))
      (node (ref "U3") (pin "B1") (pinfunction "SW_B1") (pintype "bidirectional"))
      (node (ref "U3") (pin "B2") (pinfunction "SW_B2") (pintype "bidirectional"))
    )
    (net (code "55") (name "Net-(L2-1)") (class "Default")
      (node (ref "L2") (pin "P$1") (pinfunction "1_P$1") (pintype "passive"))
      (node (ref "U10") (pin "1") (pinfunction "SW_1") (pintype "bidirectional"))
      (node (ref "U10") (pin "2") (pinfunction "SW_2") (pintype "bidirectional"))
    )
    (net (code "56") (name "Net-(L3-1)") (class "Default")
      (node (ref "L3") (pin "P$1") (pinfunction "1_P$1") (pintype "passive"))
      (node (ref "U16") (pin "1") (pinfunction "SW_1") (pintype "bidirectional"))
    )
    (net (code "57") (name "Net-(L5-1)") (class "Default")
      (node (ref "L5") (pin "P$1") (pinfunction "1_P$1") (pintype "passive"))
      (node (ref "U1") (pin "14") (pinfunction "LX_14") (pintype "bidirectional"))
    )
    (net (code "58") (name "Net-(L5-2)") (class "Default")
      (node (ref "L5") (pin "P$2") (pinfunction "2_P$2") (pintype "passive"))
      (node (ref "U1") (pin "13") (pinfunction "CS_13") (pintype "bidirectional"))
    )
    (net (code "59") (name "Net-(R1-11)") (class "Default")
      (node (ref "C3") (pin "2") (pinfunction "2_2") (pintype "passive"))
      (node (ref "R1") (pin "1") (pinfunction "11_1") (pintype "passive"))
      (node (ref "R2") (pin "1") (pinfunction "11_1") (pintype "passive"))
      (node (ref "U1") (pin "4") (pinfunction "VCC_4") (pintype "power_in"))
      (node (ref "U1") (pin "5") (pinfunction "EN_5") (pintype "bidirectional"))
    )
    (net (code "60") (name "Net-(R2-22)") (class "Default")
      (node (ref "R2") (pin "2") (pinfunction "22_2") (pintype "passive"))
      (node (ref "U1") (pin "11") (pinfunction "TS_11") (pintype "bidirectional"))
    )
    (net (code "61") (name "Net-(R3-22)") (class "Default")
      (node (ref "JP2") (pin "1") (pinfunction "1_1") (pintype "passive"))
      (node (ref "R3") (pin "2") (pinfunction "22_2") (pintype "passive"))
    )
    (net (code "62") (name "Net-(R8-11)") (class "Default")
      (node (ref "Q1") (pin "G") (pinfunction "G_G") (pintype "passive"))
      (node (ref "Q2") (pin "D") (pinfunction "D_D") (pintype "passive"))
      (node (ref "R8") (pin "1") (pinfunction "11_1") (pintype "passive"))
    )
    (net (code "63") (name "Net-(R11-11)") (class "Default")
      (node (ref "R11") (pin "1") (pinfunction "11_1") (pintype "passive"))
      (node (ref "U18") (pin "CS0") (pinfunction "CS0_CS0") (pintype "bidirectional"))
    )
    (net (code "64") (name "Net-(R12-11)") (class "Default")
      (node (ref "R12") (pin "1") (pinfunction "11_1") (pintype "passive"))
      (node (ref "U2") (pin "1") (pinfunction "REF_1") (pintype "bidirectional"))
    )
    (net (code "65") (name "Net-(R12-22)") (class "Default")
      (node (ref "R12") (pin "2") (pinfunction "22_2") (pintype "passive"))
      (node (ref "R13") (pin "1") (pinfunction "11_1") (pintype "passive"))
    )
    (net (code "66") (name "Net-(R13-22)") (class "Default")
      (node (ref "C10") (pin "1") (pinfunction "1_1") (pintype "passive"))
      (node (ref "R13") (pin "2") (pinfunction "22_2") (pintype "passive"))
    )
    (net (code "67") (name "Net-(R14-11)") (class "Default")
      (node (ref "R14") (pin "1") (pinfunction "11_1") (pintype "passive"))
      (node (ref "U18") (pin "MISO") (pinfunction "MISO_MISO") (pintype "bidirectional"))
    )
    (net (code "68") (name "Net-(R15-11)") (class "Default")
      (node (ref "R15") (pin "1") (pinfunction "11_1") (pintype "passive"))
      (node (ref "U18") (pin "GPIO9") (pinfunction "*GPIO9_GPIO9") (pintype "bidirectional"))
    )
    (net (code "69") (name "Net-(R16-11)") (class "Default")
      (node (ref "R16") (pin "1") (pinfunction "11_1") (pintype "passive"))
      (node (ref "R9") (pin "2") (pinfunction "22_2") (pintype "passive"))
      (node (ref "U2") (pin "5") (pinfunction "AIN0_5") (pintype "input"))
    )
    (net (code "70") (name "Net-(R17-22)") (class "Default")
      (node (ref "D2") (pin "C") (pinfunction "C_C") (pintype "passive"))
      (node (ref "R17") (pin "2") (pinfunction "22_2") (pintype "passive"))
    )
    (net (code "71") (name "Net-(R18-22)") (class "Default")
      (node (ref "D3") (pin "C") (pinfunction "C_C") (pintype "passive"))
      (node (ref "R18") (pin "2") (pinfunction "22_2") (pintype "passive"))
    )
    (net (code "72") (name "Net-(R19-22)") (class "Default")
      (node (ref "JP2") (pin "3") (pinfunction "3_3") (pintype "passive"))
      (node (ref "R19") (pin "2") (pinfunction "22_2") (pintype "passive"))
    )
    (net (code "73") (name "Net-(R21-11)") (class "Default")
      (node (ref "R21") (pin "1") (pinfunction "11_1") (pintype "passive"))
      (node (ref "U18") (pin "GPIO10") (pinfunction "*GPIO10_GPIO10") (pintype "bidirectional"))
    )
    (net (code "74") (name "Net-(R23-22)") (class "Default")
      (node (ref "R23") (pin "2") (pinfunction "22_2") (pintype "passive"))
      (node (ref "R5") (pin "1") (pinfunction "11_1") (pintype "passive"))
      (node (ref "U8") (pin "A") (pinfunction "A_A") (pintype "bidirectional"))
    )
    (net (code "75") (name "Net-(R24-11)") (class "Default")
      (node (ref "R24") (pin "1") (pinfunction "11_1") (pintype "passive"))
      (node (ref "R25") (pin "2") (pinfunction "22_2") (pintype "passive"))
      (node (ref "U8") (pin "B") (pinfunction "B_B") (pintype "bidirectional"))
    )
    (net (code "76") (name "Net-(R26-22)") (class "Default")
      (node (ref "R26") (pin "2") (pinfunction "22_2") (pintype "passive"))
      (node (ref "R27") (pin "1") (pinfunction "11_1") (pintype "passive"))
      (node (ref "U9") (pin "A") (pinfunction "A_A") (pintype "bidirectional"))
    )
    (net (code "77") (name "Net-(R28-11)") (class "Default")
      (node (ref "R28") (pin "1") (pinfunction "11_1") (pintype "passive"))
      (node (ref "R29") (pin "2") (pinfunction "22_2") (pintype "passive"))
      (node (ref "U9") (pin "B") (pinfunction "B_B") (pintype "bidirectional"))
    )
    (net (code "78") (name "Net-(R30-11)") (class "Default")
      (node (ref "R30") (pin "1") (pinfunction "11_1") (pintype "passive"))
      (node (ref "U18") (pin "MOSI") (pinfunction "MOSI_MOSI") (pintype "bidirectional"))
    )
    (net (code "79") (name "Net-(R31-11)") (class "Default")
      (node (ref "R31") (pin "1") (pinfunction "11_1") (pintype "passive"))
      (node (ref "U18") (pin "SCLK") (pinfunction "SCLK_SCLK") (pintype "bidirectional"))
    )
    (net (code "80") (name "Net-(R32-11)") (class "Default")
      (node (ref "D1") (pin "A") (pinfunction "A_A") (pintype "passive"))
      (node (ref "R32") (pin "1") (pinfunction "11_1") (pintype "passive"))
    )
    (net (code "81") (name "Net-(R33-11)") (class "Default")
      (node (ref "D4") (pin "A") (pinfunction "A_A") (pintype "passive"))
      (node (ref "R33") (pin "1") (pinfunction "11_1") (pintype "passive"))
    )
    (net (code "82") (name "Net-(R45-11)") (class "Default")
      (node (ref "R45") (pin "1") (pinfunction "11_1") (pintype "passive"))
      (node (ref "U6") (pin "168") (pinfunction "USB_OTGID_168") (pintype "bidirectional"))
    )
    (net (code "83") (name "Net-(R48-22)") (class "Default")
      (node (ref "R48") (pin "2") (pinfunction "22_2") (pintype "passive"))
      (node (ref "U10") (pin "13") (pinfunction "EN_13") (pintype "bidirectional"))
      (node (ref "U11") (pin "6") (pinfunction "FLAG1_6") (pintype "passive"))
    )
    (net (code "84") (name "Net-(R49-22)") (class "Default")
      (node (ref "R49") (pin "2") (pinfunction "22_2") (pintype "passive"))
      (node (ref "U11") (pin "5") (pinfunction "FLAG2_5") (pintype "passive"))
      (node (ref "U16") (pin "2") (pinfunction "EN_2") (pintype "bidirectional"))
    )
    (net (code "85") (name "Net-(R50-11)") (class "Default")
      (node (ref "R50") (pin "1") (pinfunction "11_1") (pintype "passive"))
      (node (ref "U5") (pin "63") (pinfunction "USBRBIAS_63") (pintype "input"))
    )
    (net (code "86") (name "Net-(R51-11)") (class "Default")
      (node (ref "R51") (pin "1") (pinfunction "11_1") (pintype "passive"))
      (node (ref "U5") (pin "41") (pinfunction "AUTOMDIX_EN_41") (pintype "input"))
    )
    (net (code "87") (name "Net-(R52-22)") (class "Default")
      (node (ref "R52") (pin "2") (pinfunction "22_2") (pintype "passive"))
      (node (ref "U5") (pin "50") (pinfunction "EXRES_50") (pintype "input"))
    )
    (net (code "88") (name "Net-(U1-CT)") (class "Default")
      (node (ref "C2") (pin "2") (pinfunction "2_2") (pintype "passive"))
      (node (ref "U1") (pin "7") (pinfunction "CT_7") (pintype "bidirectional"))
    )
    (net (code "89") (name "Net-(U2-AIN1)") (class "Default")
      (node (ref "J5") (pin "13") (pinfunction "13_13") (pintype "bidirectional"))
      (node (ref "U2") (pin "6") (pinfunction "AIN1_6") (pintype "input"))
    )
    (net (code "90") (name "Net-(U2-AIN2)") (class "Default")
      (node (ref "J5") (pin "14") (pinfunction "14_14") (pintype "bidirectional"))
      (node (ref "U2") (pin "7") (pinfunction "AIN2_7") (pintype "input"))
    )
    (net (code "91") (name "Net-(U2-AIN3)") (class "Default")
      (node (ref "J10") (pin "19") (pinfunction "19_19") (pintype "bidirectional"))
      (node (ref "U2") (pin "8") (pinfunction "AIN3_8") (pintype "input"))
    )
    (net (code "92") (name "Net-(U2-AIN4)") (class "Default")
      (node (ref "J10") (pin "20") (pinfunction "20_20") (pintype "bidirectional"))
      (node (ref "U2") (pin "9") (pinfunction "AIN4_9") (pintype "input"))
    )
    (net (code "93") (name "Net-(U5B-VDD18CORE)") (class "Default")
      (node (ref "C54") (pin "2") (pinfunction "2_2") (pintype "passive"))
      (node (ref "C66") (pin "2") (pinfunction "2_2") (pintype "passive"))
      (node (ref "C67") (pin "2") (pinfunction "2_2") (pintype "passive"))
      (node (ref "U5") (pin "15") (pinfunction "VDD18CORE_2_15") (pintype "power_in"))
      (node (ref "U5") (pin "38") (pinfunction "VDD18CORE_38") (pintype "power_in"))
    )
    (net (code "94") (name "Net-(U5B-VDD18ETHPLL)") (class "Default")
      (node (ref "C65") (pin "2") (pinfunction "2_2") (pintype "passive"))
      (node (ref "FB1") (pin "1") (pinfunction "1_1") (pintype "passive"))
      (node (ref "U5") (pin "48") (pinfunction "VDD18ETHPLL_48") (pintype "power_in"))
    )
    (net (code "95") (name "Net-(U6-GPIO4)") (class "Default")
      (node (ref "J8") (pin "1") (pinfunction "1_1") (pintype "bidirectional"))
      (node (ref "U6") (pin "15") (pinfunction "GPIO4_15") (pintype "bidirectional"))
    )
    (net (code "96") (name "Net-(U10-CN)") (class "Default")
      (node (ref "C6") (pin "1") (pinfunction "1_1") (pintype "bidirectional"))
      (node (ref "U10") (pin "8") (pinfunction "CN_8") (pintype "bidirectional"))
    )
    (net (code "97") (name "Net-(U10-CP)") (class "Default")
      (node (ref "C6") (pin "2") (pinfunction "2_2") (pintype "bidirectional"))
      (node (ref "U10") (pin "7") (pinfunction "CP_7") (pintype "bidirectional"))
    )
    (net (code "98") (name "Net-(U10-SS)") (class "Default")
      (node (ref "C7") (pin "2") (pinfunction "2_2") (pintype "bidirectional"))
      (node (ref "U10") (pin "9") (pinfunction "SS_9") (pintype "bidirectional"))
    )
    (net (code "99") (name "Net-(U16-CFF)") (class "Default")
      (node (ref "C18") (pin "1") (pinfunction "1_1") (pintype "passive"))
      (node (ref "U16") (pin "5") (pinfunction "CFF_5") (pintype "bidirectional"))
    )
    (net (code "100") (name "Net-(U17-(PCINT0{slash}TPIDATA)_PB0)") (class "Default")
      (node (ref "TP2") (pin "TP") (pinfunction "TP_TP") (pintype "input"))
      (node (ref "U17") (pin "1") (pinfunction "(PCINT0/TPIDATA)_PB0_1") (pintype "bidirectional"))
    )
    (net (code "101") (name "Net-(U17-PB3_(~{RESET}))") (class "Default")
      (node (ref "TP1") (pin "TP") (pinfunction "TP_TP") (pintype "input"))
      (node (ref "U17") (pin "6") (pinfunction "PB3_(~{RESET})_6") (pintype "bidirectional"))
    )
    (net (code "102") (name "Net-(U19-SPK_RN)") (class "Default")
      (node (ref "FB4") (pin "1") (pinfunction "1_1") (pintype "passive"))
      (node (ref "U19") (pin "19") (pinfunction "SPK_RN_19") (pintype "bidirectional"))
    )
    (net (code "103") (name "Net-(U19-SPK_RP)") (class "Default")
      (node (ref "FB3") (pin "1") (pinfunction "1_1") (pintype "passive"))
      (node (ref "U19") (pin "22") (pinfunction "SPK_RP_22") (pintype "bidirectional"))
    )
    (net (code "104") (name "Net-(U19-VMID)") (class "Default")
      (node (ref "C25") (pin "1") (pinfunction "1_1") (pintype "passive"))
      (node (ref "C26") (pin "1") (pinfunction "1_1") (pintype "passive"))
      (node (ref "U19") (pin "27") (pinfunction "VMID_27") (pintype "bidirectional"))
    )
    (net (code "105") (name "POWER_SEQ_EN") (class "Default")
      (node (ref "R4") (pin "2") (pinfunction "22_2") (pintype "passive"))
      (node (ref "U11") (pin "3") (pinfunction "EN_3") (pintype "input"))
    )
    (net (code "106") (name "RIN1") (class "Default")
      (node (ref "C30") (pin "2") (pinfunction "22_2") (pintype "passive"))
      (node (ref "U19") (pin "5") (pinfunction "RIN1_5") (pintype "bidirectional"))
    )
    (net (code "107") (name "RX_N") (class "Default")
      (node (ref "J10") (pin "15") (pinfunction "15_15") (pintype "bidirectional"))
      (node (ref "U5") (pin "53") (pinfunction "RXN_53") (pintype "bidirectional"))
    )
    (net (code "108") (name "RX_P") (class "Default")
      (node (ref "J10") (pin "16") (pinfunction "16_16") (pintype "bidirectional"))
      (node (ref "U5") (pin "52") (pinfunction "RXP_52") (pintype "bidirectional"))
    )
    (net (code "109") (name "SDX_CLK") (class "Default")
      (node (ref "U$2") (pin "5") (pinfunction "CLK_5") (pintype "bidirectional"))
      (node (ref "U6") (pin "10") (pinfunction "SDX_CLK_10") (pintype "bidirectional"))
    )
    (net (code "110") (name "SDX_CMD") (class "Default")
      (node (ref "U$2") (pin "3") (pinfunction "CMD_3") (pintype "bidirectional"))
      (node (ref "U6") (pin "12") (pinfunction "SDX_CMD_12") (pintype "bidirectional"))
    )
    (net (code "111") (name "SDX_D0") (class "Default")
      (node (ref "U$2") (pin "7") (pinfunction "DAT0_7") (pintype "bidirectional"))
      (node (ref "U6") (pin "16") (pinfunction "SDX_D0_16") (pintype "bidirectional"))
    )
    (net (code "112") (name "SDX_D1") (class "Default")
      (node (ref "U$2") (pin "8") (pinfunction "DAT1_8") (pintype "bidirectional"))
      (node (ref "U6") (pin "18") (pinfunction "SDX_D1_18") (pintype "bidirectional"))
    )
    (net (code "113") (name "SDX_D2") (class "Default")
      (node (ref "U$2") (pin "1") (pinfunction "DAT2_1") (pintype "bidirectional"))
      (node (ref "U6") (pin "22") (pinfunction "SDX_D2_22") (pintype "bidirectional"))
    )
    (net (code "114") (name "SDX_D3") (class "Default")
      (node (ref "U$2") (pin "2") (pinfunction "CD/DAT3_2") (pintype "bidirectional"))
      (node (ref "U6") (pin "24") (pinfunction "SDX_D3_24") (pintype "bidirectional"))
    )
    (net (code "115") (name "SD_CLK") (class "Default")
      (node (ref "R31") (pin "2") (pinfunction "22_2") (pintype "passive"))
      (node (ref "U6") (pin "75") (pinfunction "GPIO22_75") (pintype "bidirectional"))
    )
    (net (code "116") (name "SD_CMD") (class "Default")
      (node (ref "R11") (pin "2") (pinfunction "22_2") (pintype "passive"))
      (node (ref "U6") (pin "77") (pinfunction "GPIO23_77") (pintype "bidirectional"))
    )
    (net (code "117") (name "SD_D0") (class "Default")
      (node (ref "R14") (pin "2") (pinfunction "22_2") (pintype "passive"))
      (node (ref "U6") (pin "81") (pinfunction "GPIO24_81") (pintype "bidirectional"))
    )
    (net (code "118") (name "SD_D1") (class "Default")
      (node (ref "R30") (pin "2") (pinfunction "22_2") (pintype "passive"))
      (node (ref "U6") (pin "83") (pinfunction "GPIO25_83") (pintype "bidirectional"))
    )
    (net (code "119") (name "SD_D2") (class "Default")
      (node (ref "R15") (pin "2") (pinfunction "22_2") (pintype "passive"))
      (node (ref "U6") (pin "87") (pinfunction "GPIO26_87") (pintype "bidirectional"))
    )
    (net (code "120") (name "SD_D3") (class "Default")
      (node (ref "R21") (pin "2") (pinfunction "22_2") (pintype "passive"))
      (node (ref "U6") (pin "89") (pinfunction "GPIO27_89") (pintype "bidirectional"))
    )
    (net (code "121") (name "SHUTDOWN_SIG") (class "Default")
      (node (ref "R43") (pin "1") (pinfunction "11_1") (pintype "passive"))
      (node (ref "U17") (pin "4") (pinfunction "PB2_(T0/CLKO/PCINT2)_4") (pintype "bidirectional"))
      (node (ref "U6") (pin "17") (pinfunction "GPIO5_17") (pintype "bidirectional"))
    )
    (net (code "122") (name "SPI_CS0") (class "Default")
      (node (ref "J2") (pin "5") (pinfunction "CS0_5") (pintype "bidirectional"))
      (node (ref "U6") (pin "27") (pinfunction "GPIO8_27") (pintype "bidirectional"))
    )
    (net (code "123") (name "SPI_CS1") (class "Default")
      (node (ref "J2") (pin "6") (pinfunction "CS1_6") (pintype "bidirectional"))
      (node (ref "U6") (pin "23") (pinfunction "GPIO7_23") (pintype "bidirectional"))
    )
    (net (code "124") (name "SPI_MISO") (class "Default")
      (node (ref "J2") (pin "9") (pinfunction "MISO_9") (pintype "bidirectional"))
      (node (ref "U6") (pin "29") (pinfunction "GPIO9_29") (pintype "bidirectional"))
    )
    (net (code "125") (name "SPI_MOSI") (class "Default")
      (node (ref "J2") (pin "10") (pinfunction "MOSI_10") (pintype "bidirectional"))
      (node (ref "U6") (pin "33") (pinfunction "GPIO10_33") (pintype "bidirectional"))
    )
    (net (code "126") (name "SPI_SCLK") (class "Default")
      (node (ref "J2") (pin "8") (pinfunction "SCLK_8") (pintype "bidirectional"))
      (node (ref "U6") (pin "35") (pinfunction "GPIO11_35") (pintype "bidirectional"))
    )
    (net (code "127") (name "STAT1") (class "Default")
      (node (ref "R17") (pin "1") (pinfunction "11_1") (pintype "passive"))
      (node (ref "U1") (pin "9") (pinfunction "STAT1_9") (pintype "bidirectional"))
      (node (ref "U6") (pin "46") (pinfunction "GPIO32_46") (pintype "bidirectional"))
    )
    (net (code "128") (name "STAT2") (class "Default")
      (node (ref "R18") (pin "1") (pinfunction "11_1") (pintype "passive"))
      (node (ref "U1") (pin "8") (pinfunction "STAT2_8") (pintype "bidirectional"))
      (node (ref "U6") (pin "48") (pinfunction "GPIO33_48") (pintype "bidirectional"))
    )
    (net (code "129") (name "SWITCH_IN") (class "Default")
      (node (ref "C5") (pin "2") (pinfunction "2_2") (pintype "passive"))
      (node (ref "J4") (pin "2") (pinfunction "2_2") (pintype "bidirectional"))
      (node (ref "J6") (pin "1") (pinfunction "5V_1") (pintype "power_in"))
      (node (ref "Q1") (pin "S") (pinfunction "S_S") (pintype "passive"))
      (node (ref "R8") (pin "2") (pinfunction "22_2") (pintype "passive"))
      (node (ref "R9") (pin "1") (pinfunction "11_1") (pintype "passive"))
      (node (ref "U1") (pin "12") (pinfunction "BAT_12") (pintype "power_in"))
    )
    (net (code "130") (name "SWITCH_OUT") (class "Default")
      (node (ref "D6") (pin "A") (pinfunction "21_A") (pintype "passive"))
      (node (ref "J4") (pin "3") (pinfunction "3_3") (pintype "bidirectional"))
      (node (ref "U6") (pin "21") (pinfunction "GPIO6_21") (pintype "bidirectional"))
    )
    (net (code "131") (name "TX_N") (class "Default")
      (node (ref "J10") (pin "12") (pinfunction "12_12") (pintype "bidirectional"))
      (node (ref "U5") (pin "56") (pinfunction "TXN_56") (pintype "bidirectional"))
    )
    (net (code "132") (name "TX_P") (class "Default")
      (node (ref "J10") (pin "13") (pinfunction "13_13") (pintype "bidirectional"))
      (node (ref "U5") (pin "55") (pinfunction "TXP_55") (pintype "bidirectional"))
    )
    (net (code "133") (name "UART_RX") (class "Default")
      (node (ref "J1") (pin "2") (pinfunction "2_2") (pintype "bidirectional"))
      (node (ref "U6") (pin "53") (pinfunction "GPIO15_53") (pintype "bidirectional"))
    )
    (net (code "134") (name "UART_TX") (class "Default")
      (node (ref "J1") (pin "1") (pinfunction "1_1") (pintype "bidirectional"))
      (node (ref "U6") (pin "51") (pinfunction "GPIO14_51") (pintype "bidirectional"))
    )
    (net (code "135") (name "USB_D2_N") (class "Default")
      (node (ref "J9") (pin "2") (pinfunction "D-_2") (pintype "bidirectional"))
      (node (ref "U5") (pin "1") (pinfunction "USBDM2_1") (pintype "bidirectional"))
    )
    (net (code "136") (name "USB_D2_P") (class "Default")
      (node (ref "J9") (pin "3") (pinfunction "D+_3") (pintype "bidirectional"))
      (node (ref "U5") (pin "2") (pinfunction "USBDP2_2") (pintype "bidirectional"))
    )
    (net (code "137") (name "USB_D3_N") (class "Default")
      (node (ref "U5") (pin "3") (pinfunction "USBDM3_3") (pintype "bidirectional"))
    )
    (net (code "138") (name "USB_D3_P") (class "Default")
      (node (ref "U5") (pin "4") (pinfunction "USBDP3_4") (pintype "bidirectional"))
    )
    (net (code "139") (name "USB_D_N") (class "Default")
      (node (ref "U5") (pin "58") (pinfunction "USBDM0_58") (pintype "bidirectional"))
      (node (ref "U6") (pin "167") (pinfunction "USB_DM_167") (pintype "bidirectional"))
    )
    (net (code "140") (name "USB_D_P") (class "Default")
      (node (ref "U5") (pin "59") (pinfunction "USBDP0_59") (pintype "bidirectional"))
      (node (ref "U6") (pin "165") (pinfunction "USB_DP_165") (pintype "bidirectional"))
    )
    (net (code "141") (name "unconnected-(J3-D+-Pad3)") (class "Default")
      (node (ref "J3") (pin "3") (pinfunction "D+_3") (pintype "bidirectional"))
    )
    (net (code "142") (name "unconnected-(J3-D--Pad2)") (class "Default")
      (node (ref "J3") (pin "2") (pinfunction "D-_2") (pintype "bidirectional"))
    )
    (net (code "143") (name "unconnected-(J5-Pad1)") (class "Default")
      (node (ref "J5") (pin "1") (pinfunction "1_1") (pintype "bidirectional"))
    )
    (net (code "144") (name "unconnected-(J5-Pad2)") (class "Default")
      (node (ref "J5") (pin "2") (pinfunction "2_2") (pintype "bidirectional"))
    )
    (net (code "145") (name "unconnected-(J5-Pad3)") (class "Default")
      (node (ref "J5") (pin "3") (pinfunction "3_3") (pintype "bidirectional"))
    )
    (net (code "146") (name "unconnected-(J5-Pad4)") (class "Default")
      (node (ref "J5") (pin "4") (pinfunction "4_4") (pintype "bidirectional"))
    )
    (net (code "147") (name "unconnected-(J5-Pad5)") (class "Default")
      (node (ref "J5") (pin "5") (pinfunction "5_5") (pintype "bidirectional"))
    )
    (net (code "148") (name "unconnected-(J5-Pad6)") (class "Default")
      (node (ref "J5") (pin "6") (pinfunction "6_6") (pintype "bidirectional"))
    )
    (net (code "149") (name "unconnected-(J5-Pad7)") (class "Default")
      (node (ref "J5") (pin "7") (pinfunction "7_7") (pintype "bidirectional"))
    )
    (net (code "150") (name "unconnected-(J5-Pad8)") (class "Default")
      (node (ref "J5") (pin "8") (pinfunction "8_8") (pintype "bidirectional"))
    )
    (net (code "151") (name "unconnected-(J5-Pad9)") (class "Default")
      (node (ref "J5") (pin "9") (pinfunction "9_9") (pintype "bidirectional"))
    )
    (net (code "152") (name "unconnected-(J5-Pad10)") (class "Default")
      (node (ref "J5") (pin "10") (pinfunction "10_10") (pintype "bidirectional"))
    )
    (net (code "153") (name "unconnected-(J5-Pad16)") (class "Default")
      (node (ref "J5") (pin "16") (pinfunction "16_16") (pintype "bidirectional"))
    )
    (net (code "154") (name "unconnected-(J5-Pad17)") (class "Default")
      (node (ref "J5") (pin "17") (pinfunction "17_17") (pintype "bidirectional"))
    )
    (net (code "155") (name "unconnected-(J5-Pad18)") (class "Default")
      (node (ref "J5") (pin "18") (pinfunction "18_18") (pintype "bidirectional"))
    )
    (net (code "156") (name "unconnected-(J5-Pad19)") (class "Default")
      (node (ref "J5") (pin "19") (pinfunction "19_19") (pintype "bidirectional"))
    )
    (net (code "157") (name "unconnected-(J5-Pad20)") (class "Default")
      (node (ref "J5") (pin "20") (pinfunction "20_20") (pintype "bidirectional"))
    )
    (net (code "158") (name "unconnected-(J7-+5V-Pad18)") (class "Default")
      (node (ref "J7") (pin "18") (pinfunction "+5V_18") (pintype "bidirectional"))
    )
    (net (code "159") (name "unconnected-(J7-NC-Pad14)") (class "Default")
      (node (ref "J7") (pin "14") (pinfunction "NC_14") (pintype "bidirectional"))
    )
    (net (code "160") (name "unconnected-(J10-Pad3)") (class "Default")
      (node (ref "J10") (pin "3") (pinfunction "3_3") (pintype "bidirectional"))
    )
    (net (code "161") (name "unconnected-(J10-Pad4)") (class "Default")
      (node (ref "J10") (pin "4") (pinfunction "4_4") (pintype "bidirectional"))
    )
    (net (code "162") (name "unconnected-(J10-Pad5)") (class "Default")
      (node (ref "J10") (pin "5") (pinfunction "5_5") (pintype "bidirectional"))
    )
    (net (code "163") (name "unconnected-(J10-Pad6)") (class "Default")
      (node (ref "J10") (pin "6") (pinfunction "6_6") (pintype "bidirectional"))
    )
    (net (code "164") (name "unconnected-(J10-Pad7)") (class "Default")
      (node (ref "J10") (pin "7") (pinfunction "7_7") (pintype "bidirectional"))
    )
    (net (code "165") (name "unconnected-(J10-Pad8)") (class "Default")
      (node (ref "J10") (pin "8") (pinfunction "8_8") (pintype "bidirectional"))
    )
    (net (code "166") (name "unconnected-(J10-Pad9)") (class "Default")
      (node (ref "J10") (pin "9") (pinfunction "9_9") (pintype "bidirectional"))
    )
    (net (code "167") (name "unconnected-(J10-Pad10)") (class "Default")
      (node (ref "J10") (pin "10") (pinfunction "10_10") (pintype "bidirectional"))
    )
    (net (code "168") (name "unconnected-(U2-AIN7-Pad12)") (class "Default")
      (node (ref "U2") (pin "12") (pinfunction "AIN7_12") (pintype "input"))
    )
    (net (code "169") (name "unconnected-(U2-NC-Pad4)") (class "Default")
      (node (ref "U2") (pin "4") (pinfunction "NC_4") (pintype "no_connect"))
    )
    (net (code "170") (name "unconnected-(U2-NC_2-Pad2)") (class "Default")
      (node (ref "U2") (pin "2") (pinfunction "NC_2_2") (pintype "no_connect"))
    )
    (net (code "171") (name "unconnected-(U2-NC_3-Pad3)") (class "Default")
      (node (ref "U2") (pin "3") (pinfunction "NC_3_3") (pintype "no_connect"))
    )
    (net (code "172") (name "unconnected-(U3-BP-PadC3)") (class "Default")
      (node (ref "U3") (pin "C3") (pinfunction "BP_C3") (pintype "input"))
    )
    (net (code "173") (name "unconnected-(U5A-CLK24_OUT-Pad45)") (class "Default")
      (node (ref "U5") (pin "45") (pinfunction "CLK24_OUT_45") (pintype "output"))
    )
    (net (code "174") (name "unconnected-(U5A-EECLK-Pad23)") (class "Default")
      (node (ref "U5") (pin "23") (pinfunction "EECLK_23") (pintype "output"))
    )
    (net (code "175") (name "unconnected-(U5A-EECS-Pad24)") (class "Default")
      (node (ref "U5") (pin "24") (pinfunction "EECS_24") (pintype "output"))
    )
    (net (code "176") (name "unconnected-(U5A-EEDI-Pad26)") (class "Default")
      (node (ref "U5") (pin "26") (pinfunction "EEDI_26") (pintype "input"))
    )
    (net (code "177") (name "unconnected-(U5A-EEDO-Pad25)") (class "Default")
      (node (ref "U5") (pin "25") (pinfunction "EEDO_25") (pintype "output"))
    )
    (net (code "178") (name "unconnected-(U5A-GPIO3-Pad35)") (class "Default")
      (node (ref "U5") (pin "35") (pinfunction "GPIO3_35") (pintype "bidirectional"))
    )
    (net (code "179") (name "unconnected-(U5A-GPIO4-Pad36)") (class "Default")
      (node (ref "U5") (pin "36") (pinfunction "GPIO4_36") (pintype "bidirectional"))
    )
    (net (code "180") (name "unconnected-(U5A-GPIO5-Pad37)") (class "Default")
      (node (ref "U5") (pin "37") (pinfunction "GPIO5_37") (pintype "bidirectional"))
    )
    (net (code "181") (name "unconnected-(U5A-GPIO6-Pad42)") (class "Default")
      (node (ref "U5") (pin "42") (pinfunction "GPIO6_42") (pintype "bidirectional"))
    )
    (net (code "182") (name "unconnected-(U5A-GPIO7-Pad43)") (class "Default")
      (node (ref "U5") (pin "43") (pinfunction "GPIO7_43") (pintype "bidirectional"))
    )
    (net (code "183") (name "unconnected-(U5A-NFDX_LED{slash}GPIO0-Pad20)") (class "Default")
      (node (ref "U5") (pin "20") (pinfunction "NFDX_LED/GPIO0_20") (pintype "bidirectional"))
    )
    (net (code "184") (name "unconnected-(U5A-NLNKA_LED{slash}GPIO1-Pad21)") (class "Default")
      (node (ref "U5") (pin "21") (pinfunction "NLNKA_LED/GPIO1_21") (pintype "bidirectional"))
    )
    (net (code "185") (name "unconnected-(U5A-NRESET-Pad12)") (class "Default")
      (node (ref "U5") (pin "12") (pinfunction "NRESET_12") (pintype "input"))
    )
    (net (code "186") (name "unconnected-(U5A-NSPD_LED{slash}GPIO2-Pad22)") (class "Default")
      (node (ref "U5") (pin "22") (pinfunction "NSPD_LED/GPIO2_22") (pintype "bidirectional"))
    )
    (net (code "187") (name "unconnected-(U5A-NTRST-Pad28)") (class "Default")
      (node (ref "U5") (pin "28") (pinfunction "NTRST_28") (pintype "input"))
    )
    (net (code "188") (name "unconnected-(U5A-PRTCTL3-Pad16)") (class "Default")
      (node (ref "U5") (pin "16") (pinfunction "PRTCTL3_16") (pintype "bidirectional"))
    )
    (net (code "189") (name "unconnected-(U5A-PRTXTL2-Pad14)") (class "Default")
      (node (ref "U5") (pin "14") (pinfunction "PRTXTL2_14") (pintype "bidirectional"))
    )
    (net (code "190") (name "unconnected-(U5A-TCK-Pad32)") (class "Default")
      (node (ref "U5") (pin "32") (pinfunction "TCK_32") (pintype "input"))
    )
    (net (code "191") (name "unconnected-(U5A-TDI-Pad30)") (class "Default")
      (node (ref "U5") (pin "30") (pinfunction "TDI_30") (pintype "input"))
    )
    (net (code "192") (name "unconnected-(U5A-TDO-Pad31)") (class "Default")
      (node (ref "U5") (pin "31") (pinfunction "TDO_31") (pintype "output"))
    )
    (net (code "193") (name "unconnected-(U5A-TEST1-Pad13)") (class "Default")
      (node (ref "U5") (pin "13") (pinfunction "TEST1_13") (pintype "passive"))
    )
    (net (code "194") (name "unconnected-(U5A-TEST4-Pad47)") (class "Default")
      (node (ref "U5") (pin "47") (pinfunction "TEST4_47") (pintype "passive"))
    )
    (net (code "195") (name "unconnected-(U5A-TMS-Pad29)") (class "Default")
      (node (ref "U5") (pin "29") (pinfunction "TMS_29") (pintype "input"))
    )
    (net (code "196") (name "unconnected-(U5A-XO-Pad60)") (class "Default")
      (node (ref "U5") (pin "60") (pinfunction "XO_60") (pintype "output"))
    )
    (net (code "197") (name "unconnected-(U5B-NC-Pad18)") (class "Default")
      (node (ref "U5") (pin "18") (pinfunction "NC_18") (pintype "no_connect"))
    )
    (net (code "198") (name "unconnected-(U5B-NC_2-Pad6)") (class "Default")
      (node (ref "U5") (pin "6") (pinfunction "NC_2_6") (pintype "no_connect"))
    )
    (net (code "199") (name "unconnected-(U5B-NC_3-Pad7)") (class "Default")
      (node (ref "U5") (pin "7") (pinfunction "NC_3_7") (pintype "no_connect"))
    )
    (net (code "200") (name "unconnected-(U5B-NC_4-Pad8)") (class "Default")
      (node (ref "U5") (pin "8") (pinfunction "NC_4_8") (pintype "no_connect"))
    )
    (net (code "201") (name "unconnected-(U5B-NC_5-Pad9)") (class "Default")
      (node (ref "U5") (pin "9") (pinfunction "NC_5_9") (pintype "no_connect"))
    )
    (net (code "202") (name "unconnected-(U5B-NC_6-Pad17)") (class "Default")
      (node (ref "U5") (pin "17") (pinfunction "NC_6_17") (pintype "no_connect"))
    )
    (net (code "203") (name "unconnected-(U6-CAM0_CN-Pad144)") (class "Default")
      (node (ref "U6") (pin "144") (pinfunction "CAM0_CN_144") (pintype "bidirectional"))
    )
    (net (code "204") (name "unconnected-(U6-CAM0_CP-Pad142)") (class "Default")
      (node (ref "U6") (pin "142") (pinfunction "CAM0_CP_142") (pintype "bidirectional"))
    )
    (net (code "205") (name "unconnected-(U6-CAM0_DN0-Pad138)") (class "Default")
      (node (ref "U6") (pin "138") (pinfunction "CAM0_DN0_138") (pintype "bidirectional"))
    )
    (net (code "206") (name "unconnected-(U6-CAM0_DN1-Pad150)") (class "Default")
      (node (ref "U6") (pin "150") (pinfunction "CAM0_DN1_150") (pintype "bidirectional"))
    )
    (net (code "207") (name "unconnected-(U6-CAM0_DP0-Pad136)") (class "Default")
      (node (ref "U6") (pin "136") (pinfunction "CAM0_DP0_136") (pintype "bidirectional"))
    )
    (net (code "208") (name "unconnected-(U6-CAM0_DP1-Pad148)") (class "Default")
      (node (ref "U6") (pin "148") (pinfunction "CAM0_DP1_148") (pintype "bidirectional"))
    )
    (net (code "209") (name "unconnected-(U6-CAM1_CN-Pad149)") (class "Default")
      (node (ref "U6") (pin "149") (pinfunction "CAM1_CN_149") (pintype "bidirectional"))
    )
    (net (code "210") (name "unconnected-(U6-CAM1_CP-Pad147)") (class "Default")
      (node (ref "U6") (pin "147") (pinfunction "CAM1_CP_147") (pintype "bidirectional"))
    )
    (net (code "211") (name "unconnected-(U6-CAM1_DN0-Pad161)") (class "Default")
      (node (ref "U6") (pin "161") (pinfunction "CAM1_DN0_161") (pintype "bidirectional"))
    )
    (net (code "212") (name "unconnected-(U6-CAM1_DN1-Pad155)") (class "Default")
      (node (ref "U6") (pin "155") (pinfunction "CAM1_DN1_155") (pintype "bidirectional"))
    )
    (net (code "213") (name "unconnected-(U6-CAM1_DN2-Pad143)") (class "Default")
      (node (ref "U6") (pin "143") (pinfunction "CAM1_DN2_143") (pintype "bidirectional"))
    )
    (net (code "214") (name "unconnected-(U6-CAM1_DN3-Pad137)") (class "Default")
      (node (ref "U6") (pin "137") (pinfunction "CAM1_DN3_137") (pintype "bidirectional"))
    )
    (net (code "215") (name "unconnected-(U6-CAM1_DP0-Pad159)") (class "Default")
      (node (ref "U6") (pin "159") (pinfunction "CAM1_DP0_159") (pintype "bidirectional"))
    )
    (net (code "216") (name "unconnected-(U6-CAM1_DP1-Pad153)") (class "Default")
      (node (ref "U6") (pin "153") (pinfunction "CAM1_DP1_153") (pintype "bidirectional"))
    )
    (net (code "217") (name "unconnected-(U6-CAM1_DP2-Pad141)") (class "Default")
      (node (ref "U6") (pin "141") (pinfunction "CAM1_DP2_141") (pintype "bidirectional"))
    )
    (net (code "218") (name "unconnected-(U6-CAM1_DP3-Pad135)") (class "Default")
      (node (ref "U6") (pin "135") (pinfunction "CAM1_DP3_135") (pintype "bidirectional"))
    )
    (net (code "219") (name "unconnected-(U6-DSI0_CN-Pad105)") (class "Default")
      (node (ref "U6") (pin "105") (pinfunction "DSI0_CN_105") (pintype "bidirectional"))
    )
    (net (code "220") (name "unconnected-(U6-DSI0_CP-Pad107)") (class "Default")
      (node (ref "U6") (pin "107") (pinfunction "DSI0_CP_107") (pintype "bidirectional"))
    )
    (net (code "221") (name "unconnected-(U6-DSI0_DN0-Pad99)") (class "Default")
      (node (ref "U6") (pin "99") (pinfunction "DSI0_DN0_99") (pintype "bidirectional"))
    )
    (net (code "222") (name "unconnected-(U6-DSI0_DN1-Pad93)") (class "Default")
      (node (ref "U6") (pin "93") (pinfunction "DSI0_DN1_93") (pintype "bidirectional"))
    )
    (net (code "223") (name "unconnected-(U6-DSI0_DP0-Pad101)") (class "Default")
      (node (ref "U6") (pin "101") (pinfunction "DSI0_DP0_101") (pintype "bidirectional"))
    )
    (net (code "224") (name "unconnected-(U6-DSI0_DP1-Pad95)") (class "Default")
      (node (ref "U6") (pin "95") (pinfunction "DSI0_DP1_95") (pintype "bidirectional"))
    )
    (net (code "225") (name "unconnected-(U6-DSI1_CN-Pad102)") (class "Default")
      (node (ref "U6") (pin "102") (pinfunction "DSI1_CN_102") (pintype "bidirectional"))
    )
    (net (code "226") (name "unconnected-(U6-DSI1_CP-Pad100)") (class "Default")
      (node (ref "U6") (pin "100") (pinfunction "DSI1_CP_100") (pintype "bidirectional"))
    )
    (net (code "227") (name "unconnected-(U6-DSI1_DN0-Pad96)") (class "Default")
      (node (ref "U6") (pin "96") (pinfunction "DSI1_DN0_96") (pintype "bidirectional"))
    )
    (net (code "228") (name "unconnected-(U6-DSI1_DN1-Pad120)") (class "Default")
      (node (ref "U6") (pin "120") (pinfunction "DSI1_DN1_120") (pintype "bidirectional"))
    )
    (net (code "229") (name "unconnected-(U6-DSI1_DN2-Pad114)") (class "Default")
      (node (ref "U6") (pin "114") (pinfunction "DSI1_DN2_114") (pintype "bidirectional"))
    )
    (net (code "230") (name "unconnected-(U6-DSI1_DN3-Pad108)") (class "Default")
      (node (ref "U6") (pin "108") (pinfunction "DSI1_DN3_108") (pintype "bidirectional"))
    )
    (net (code "231") (name "unconnected-(U6-DSI1_DP0-Pad94)") (class "Default")
      (node (ref "U6") (pin "94") (pinfunction "DSI1_DP0_94") (pintype "bidirectional"))
    )
    (net (code "232") (name "unconnected-(U6-DSI1_DP1-Pad118)") (class "Default")
      (node (ref "U6") (pin "118") (pinfunction "DSI1_DP1_118") (pintype "bidirectional"))
    )
    (net (code "233") (name "unconnected-(U6-DSI1_DP2-Pad112)") (class "Default")
      (node (ref "U6") (pin "112") (pinfunction "DSI1_DP2_112") (pintype "bidirectional"))
    )
    (net (code "234") (name "unconnected-(U6-DSI1_DP3-Pad106)") (class "Default")
      (node (ref "U6") (pin "106") (pinfunction "DSI1_DP3_106") (pintype "bidirectional"))
    )
    (net (code "235") (name "unconnected-(U6-GPIO12-Pad45)") (class "Default")
      (node (ref "U6") (pin "45") (pinfunction "GPIO12_45") (pintype "bidirectional"))
    )
    (net (code "236") (name "unconnected-(U6-GPIO13-Pad47)") (class "Default")
      (node (ref "U6") (pin "47") (pinfunction "GPIO13_47") (pintype "bidirectional"))
    )
    (net (code "237") (name "unconnected-(U6-GPIO16-Pad57)") (class "Default")
      (node (ref "U6") (pin "57") (pinfunction "GPIO16_57") (pintype "bidirectional"))
    )
    (net (code "238") (name "unconnected-(U6-GPIO17-Pad59)") (class "Default")
      (node (ref "U6") (pin "59") (pinfunction "GPIO17_59") (pintype "bidirectional"))
    )
    (net (code "239") (name "unconnected-(U6-GPIO29-Pad30)") (class "Default")
      (node (ref "U6") (pin "30") (pinfunction "GPIO29_30") (pintype "bidirectional"))
    )
    (net (code "240") (name "unconnected-(U6-GPIO30-Pad34)") (class "Default")
      (node (ref "U6") (pin "34") (pinfunction "GPIO30_34") (pintype "bidirectional"))
    )
    (net (code "241") (name "unconnected-(U6-GPIO31-Pad36)") (class "Default")
      (node (ref "U6") (pin "36") (pinfunction "GPIO31_36") (pintype "bidirectional"))
    )
    (net (code "242") (name "unconnected-(U6-GPIO34-Pad52)") (class "Default")
      (node (ref "U6") (pin "52") (pinfunction "GPIO34_52") (pintype "bidirectional"))
    )
    (net (code "243") (name "unconnected-(U6-GPIO35-Pad54)") (class "Default")
      (node (ref "U6") (pin "54") (pinfunction "GPIO35_54") (pintype "bidirectional"))
    )
    (net (code "244") (name "unconnected-(U6-GPIO41-Pad72)") (class "Default")
      (node (ref "U6") (pin "72") (pinfunction "GPIO41_72") (pintype "bidirectional"))
    )
    (net (code "245") (name "unconnected-(U6-GPIO45-Pad84)") (class "Default")
      (node (ref "U6") (pin "84") (pinfunction "GPIO45_84") (pintype "bidirectional"))
    )
    (net (code "246") (name "unconnected-(U6-NC-Pad124)") (class "Default")
      (node (ref "U6") (pin "124") (pinfunction "NC_124") (pintype "bidirectional"))
    )
    (net (code "247") (name "unconnected-(U6-NC-Pad126)") (class "Default")
      (node (ref "U6") (pin "126") (pinfunction "NC_126") (pintype "bidirectional"))
    )
    (net (code "248") (name "unconnected-(U6-NC-Pad128)") (class "Default")
      (node (ref "U6") (pin "128") (pinfunction "NC_128") (pintype "bidirectional"))
    )
    (net (code "249") (name "unconnected-(U6-NC-Pad130)") (class "Default")
      (node (ref "U6") (pin "130") (pinfunction "NC_130") (pintype "bidirectional"))
    )
    (net (code "250") (name "unconnected-(U6-NC-Pad132)") (class "Default")
      (node (ref "U6") (pin "132") (pinfunction "NC_132") (pintype "bidirectional"))
    )
    (net (code "251") (name "unconnected-(U6-NC-Pad154)") (class "Default")
      (node (ref "U6") (pin "154") (pinfunction "NC_154") (pintype "bidirectional"))
    )
    (net (code "252") (name "unconnected-(U6-NC-Pad156)") (class "Default")
      (node (ref "U6") (pin "156") (pinfunction "NC_156") (pintype "bidirectional"))
    )
    (net (code "253") (name "unconnected-(U6-NC-Pad158)") (class "Default")
      (node (ref "U6") (pin "158") (pinfunction "NC_158") (pintype "bidirectional"))
    )
    (net (code "254") (name "unconnected-(U6-NC-Pad160)") (class "Default")
      (node (ref "U6") (pin "160") (pinfunction "NC_160") (pintype "bidirectional"))
    )
    (net (code "255") (name "unconnected-(U6-NC-Pad162)") (class "Default")
      (node (ref "U6") (pin "162") (pinfunction "NC_162") (pintype "bidirectional"))
    )
    (net (code "256") (name "unconnected-(U6-RUN-Pad177)") (class "Default")
      (node (ref "U6") (pin "177") (pinfunction "RUN_177") (pintype "bidirectional"))
    )
    (net (code "257") (name "unconnected-(U6-TVDAC-Pad166)") (class "Default")
      (node (ref "U6") (pin "166") (pinfunction "TVDAC_166") (pintype "bidirectional"))
    )
    (net (code "258") (name "unconnected-(U6-VC_TCK-Pad180)") (class "Default")
      (node (ref "U6") (pin "180") (pinfunction "VC_TCK_180") (pintype "bidirectional"))
    )
    (net (code "259") (name "unconnected-(U6-VC_TDI-Pad174)") (class "Default")
      (node (ref "U6") (pin "174") (pinfunction "VC_TDI_174") (pintype "bidirectional"))
    )
    (net (code "260") (name "unconnected-(U6-VC_TDO-Pad178)") (class "Default")
      (node (ref "U6") (pin "178") (pinfunction "VC_TDO_178") (pintype "bidirectional"))
    )
    (net (code "261") (name "unconnected-(U6-VC_TMS-Pad176)") (class "Default")
      (node (ref "U6") (pin "176") (pinfunction "VC_TMS_176") (pintype "bidirectional"))
    )
    (net (code "262") (name "unconnected-(U6-VC_TRST_N-Pad172)") (class "Default")
      (node (ref "U6") (pin "172") (pinfunction "VC_TRST_N_172") (pintype "bidirectional"))
    )
    (net (code "263") (name "unconnected-(U6-VDD_CORE-Pad179)") (class "Default")
      (node (ref "U6") (pin "179") (pinfunction "VDD_CORE_179") (pintype "bidirectional"))
    )
    (net (code "264") (name "unconnected-(U10-PG-Pad4)") (class "Default")
      (node (ref "U10") (pin "4") (pinfunction "PG_4") (pintype "bidirectional"))
    )
    (net (code "265") (name "unconnected-(U11-FLAG3-Pad4)") (class "Default")
      (node (ref "U11") (pin "4") (pinfunction "FLAG3_4") (pintype "passive"))
    )
    (net (code "266") (name "unconnected-(U12-NC-Pad3)") (class "Default")
      (node (ref "U12") (pin "3") (pinfunction "NC_3") (pintype "no_connect"))
    )
    (net (code "267") (name "unconnected-(U12-NC_2-Pad4)") (class "Default")
      (node (ref "U12") (pin "4") (pinfunction "NC_2_4") (pintype "no_connect"))
    )
    (net (code "268") (name "unconnected-(U12-NC_3-Pad5)") (class "Default")
      (node (ref "U12") (pin "5") (pinfunction "NC_3_5") (pintype "bidirectional"))
    )
    (net (code "269") (name "unconnected-(U16-NC-Pad3)") (class "Default")
      (node (ref "U16") (pin "3") (pinfunction "NC_3") (pintype "bidirectional"))
    )
    (net (code "270") (name "unconnected-(U18-PadADC)") (class "Default")
      (node (ref "U18") (pin "ADC") (pinfunction "ADC_ADC") (pintype "bidirectional"))
    )
    (net (code "271") (name "unconnected-(U18-PadGPIO0)") (class "Default")
      (node (ref "U18") (pin "GPIO0") (pinfunction "GPIO0_GPIO0") (pintype "bidirectional"))
    )
    (net (code "272") (name "unconnected-(U18-PadGPIO2)") (class "Default")
      (node (ref "U18") (pin "GPIO2") (pinfunction "GPIO2_GPIO2") (pintype "bidirectional"))
    )
    (net (code "273") (name "unconnected-(U18-PadGPIO4)") (class "Default")
      (node (ref "U18") (pin "GPIO4") (pinfunction "GPIO4_GPIO4") (pintype "bidirectional"))
    )
    (net (code "274") (name "unconnected-(U18-PadGPIO5)") (class "Default")
      (node (ref "U18") (pin "GPIO5") (pinfunction "GPIO5_GPIO5") (pintype "bidirectional"))
    )
    (net (code "275") (name "unconnected-(U18-PadGPIO12)") (class "Default")
      (node (ref "U18") (pin "GPIO12") (pinfunction "GPIO12_GPIO12") (pintype "bidirectional"))
    )
    (net (code "276") (name "unconnected-(U18-PadGPIO13)") (class "Default")
      (node (ref "U18") (pin "GPIO13") (pinfunction "GPIO13_GPIO13") (pintype "bidirectional"))
    )
    (net (code "277") (name "unconnected-(U18-PadGPIO14)") (class "Default")
      (node (ref "U18") (pin "GPIO14") (pinfunction "GPIO14_GPIO14") (pintype "bidirectional"))
    )
    (net (code "278") (name "unconnected-(U18-PadGPIO15)") (class "Default")
      (node (ref "U18") (pin "GPIO15") (pinfunction "GPIO15_GPIO15") (pintype "bidirectional"))
    )
    (net (code "279") (name "unconnected-(U18-PadRESET)") (class "Default")
      (node (ref "U18") (pin "RESET") (pinfunction "RESET_RESET") (pintype "bidirectional"))
    )
    (net (code "280") (name "unconnected-(U18-RX-PadRXD0)") (class "Default")
      (node (ref "U18") (pin "RXD0") (pinfunction "RX_RXD0") (pintype "bidirectional"))
    )
    (net (code "281") (name "unconnected-(U18-TX-PadTXD0)") (class "Default")
      (node (ref "U18") (pin "TXD0") (pinfunction "TX_TXD0") (pintype "bidirectional"))
    )
    (net (code "282") (name "unconnected-(U19-HP_L-Pad31)") (class "Default")
      (node (ref "U19") (pin "31") (pinfunction "HP_L_31") (pintype "bidirectional"))
    )
    (net (code "283") (name "unconnected-(U19-HP_R-Pad29)") (class "Default")
      (node (ref "U19") (pin "29") (pinfunction "HP_R_29") (pintype "bidirectional"))
    )
    (net (code "284") (name "unconnected-(U19-LIN2-Pad3)") (class "Default")
      (node (ref "U19") (pin "3") (pinfunction "LIN2_3") (pintype "bidirectional"))
    )
    (net (code "285") (name "unconnected-(U19-LIN3-Pad2)") (class "Default")
      (node (ref "U19") (pin "2") (pinfunction "LIN3_2") (pintype "bidirectional"))
    )
    (net (code "286") (name "unconnected-(U19-MICBIAS-Pad1)") (class "Default")
      (node (ref "U19") (pin "1") (pinfunction "MICBIAS_1") (pintype "bidirectional"))
    )
    (net (code "287") (name "unconnected-(U19-OUT3-Pad30)") (class "Default")
      (node (ref "U19") (pin "30") (pinfunction "OUT3_30") (pintype "bidirectional"))
    )
    (net (code "288") (name "unconnected-(U19-RIN2-Pad6)") (class "Default")
      (node (ref "U19") (pin "6") (pinfunction "RIN2_6") (pintype "bidirectional"))
    )
    (net (code "289") (name "unconnected-(U19-RIN3-Pad7)") (class "Default")
      (node (ref "U19") (pin "7") (pinfunction "RIN3_7") (pintype "bidirectional"))
    )
    (net (code "290") (name "unconnected-(U19-SPK_LN-Pad23)") (class "Default")
      (node (ref "U19") (pin "23") (pinfunction "SPK_LN_23") (pintype "bidirectional"))
    )
    (net (code "291") (name "unconnected-(U19-SPK_LP-Pad25)") (class "Default")
      (node (ref "U19") (pin "25") (pinfunction "SPK_LP_25") (pintype "bidirectional"))
    )
  )
)
